# RF08old.net
KiCad netlist of a schematic drawn in EAGLE
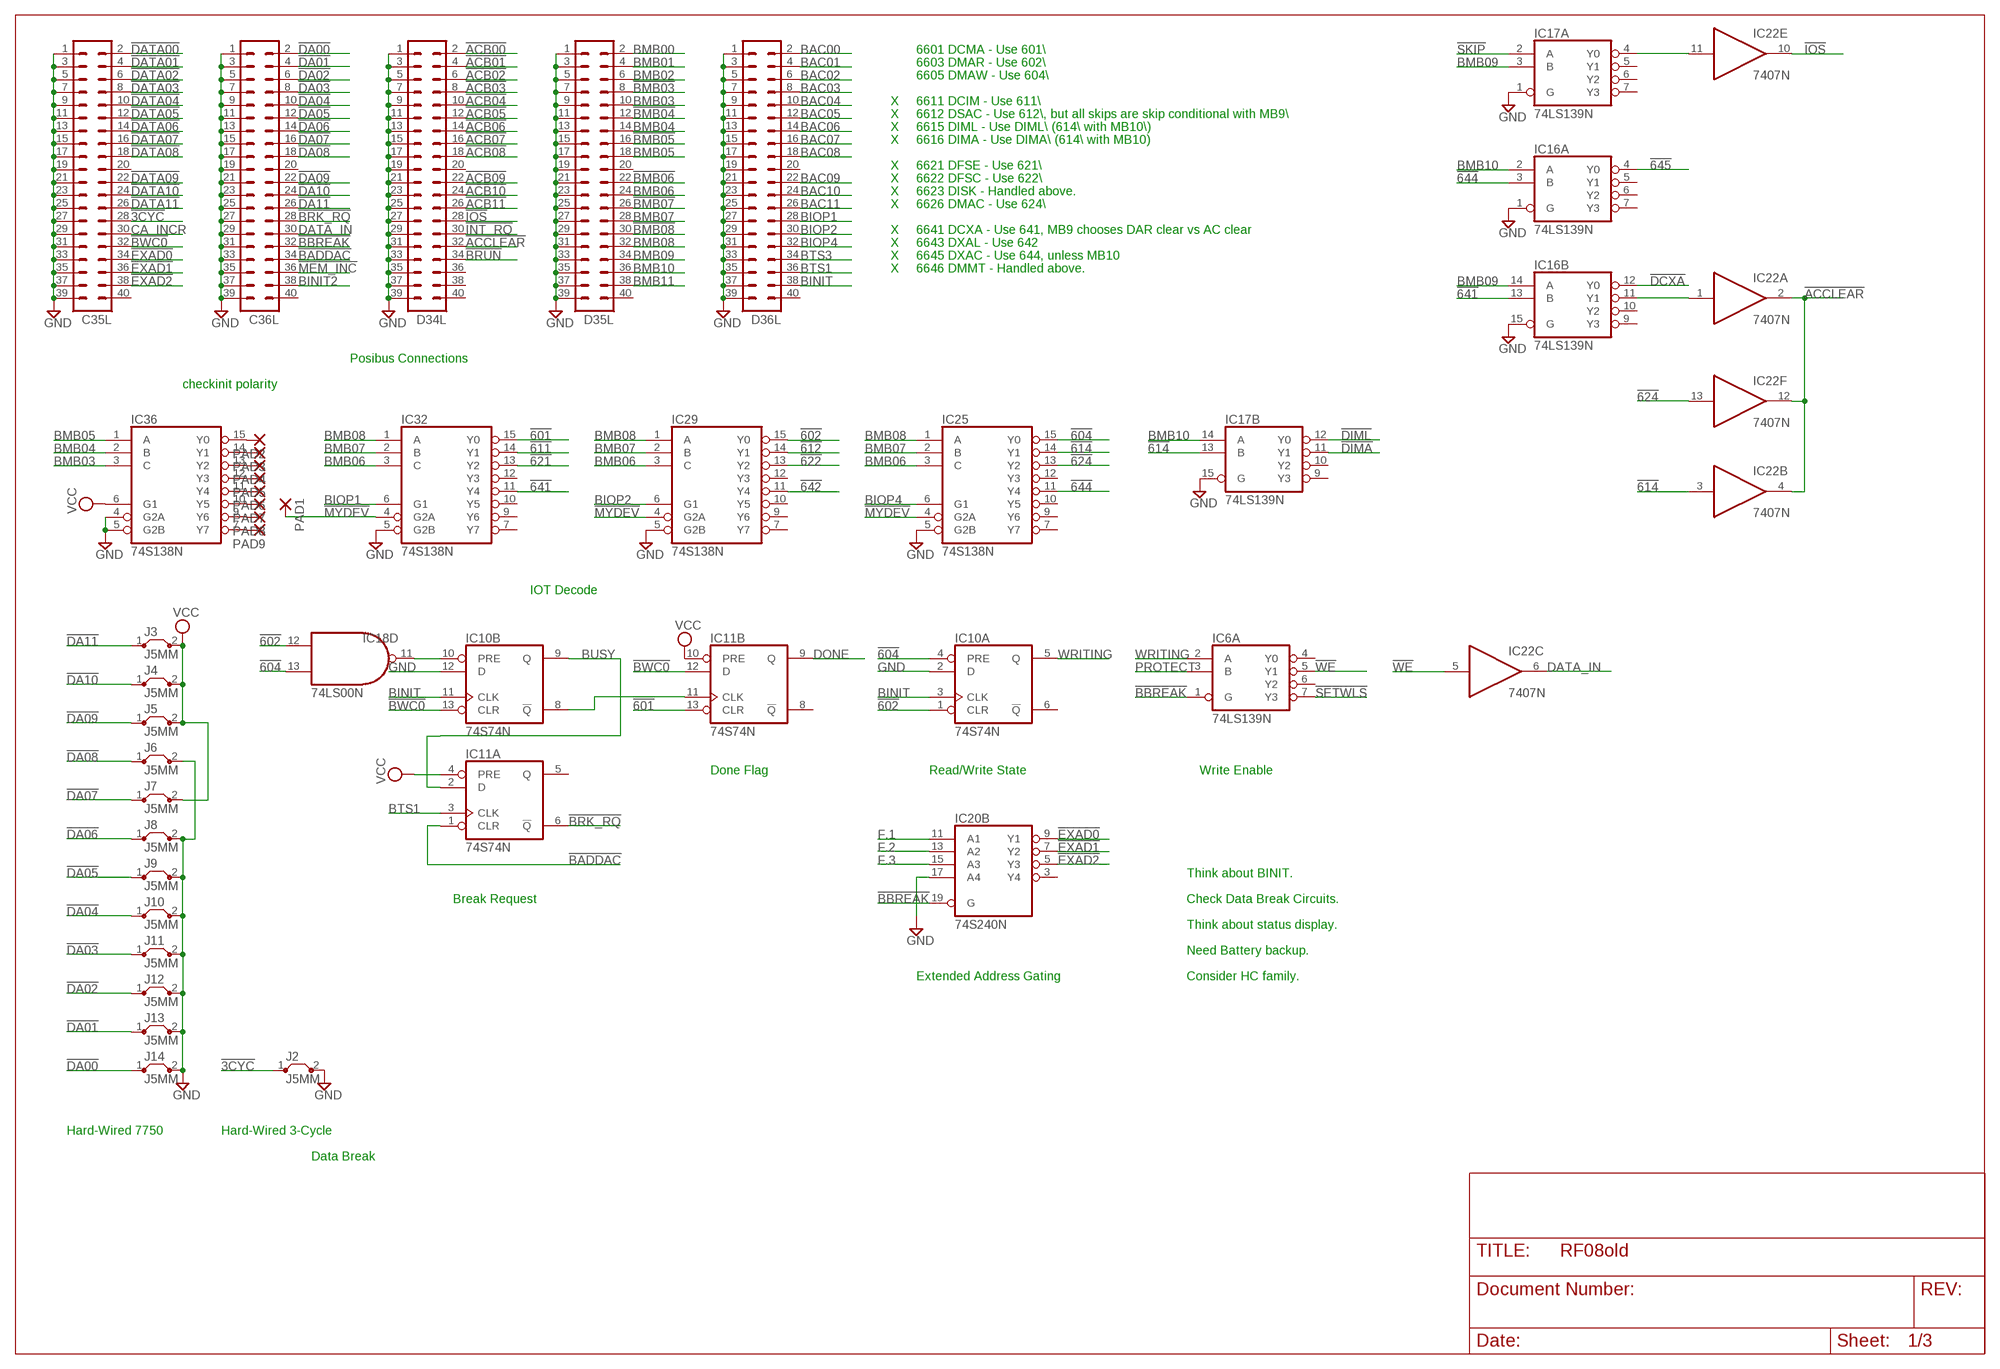
[diagram p0: schematic, sheet 1]
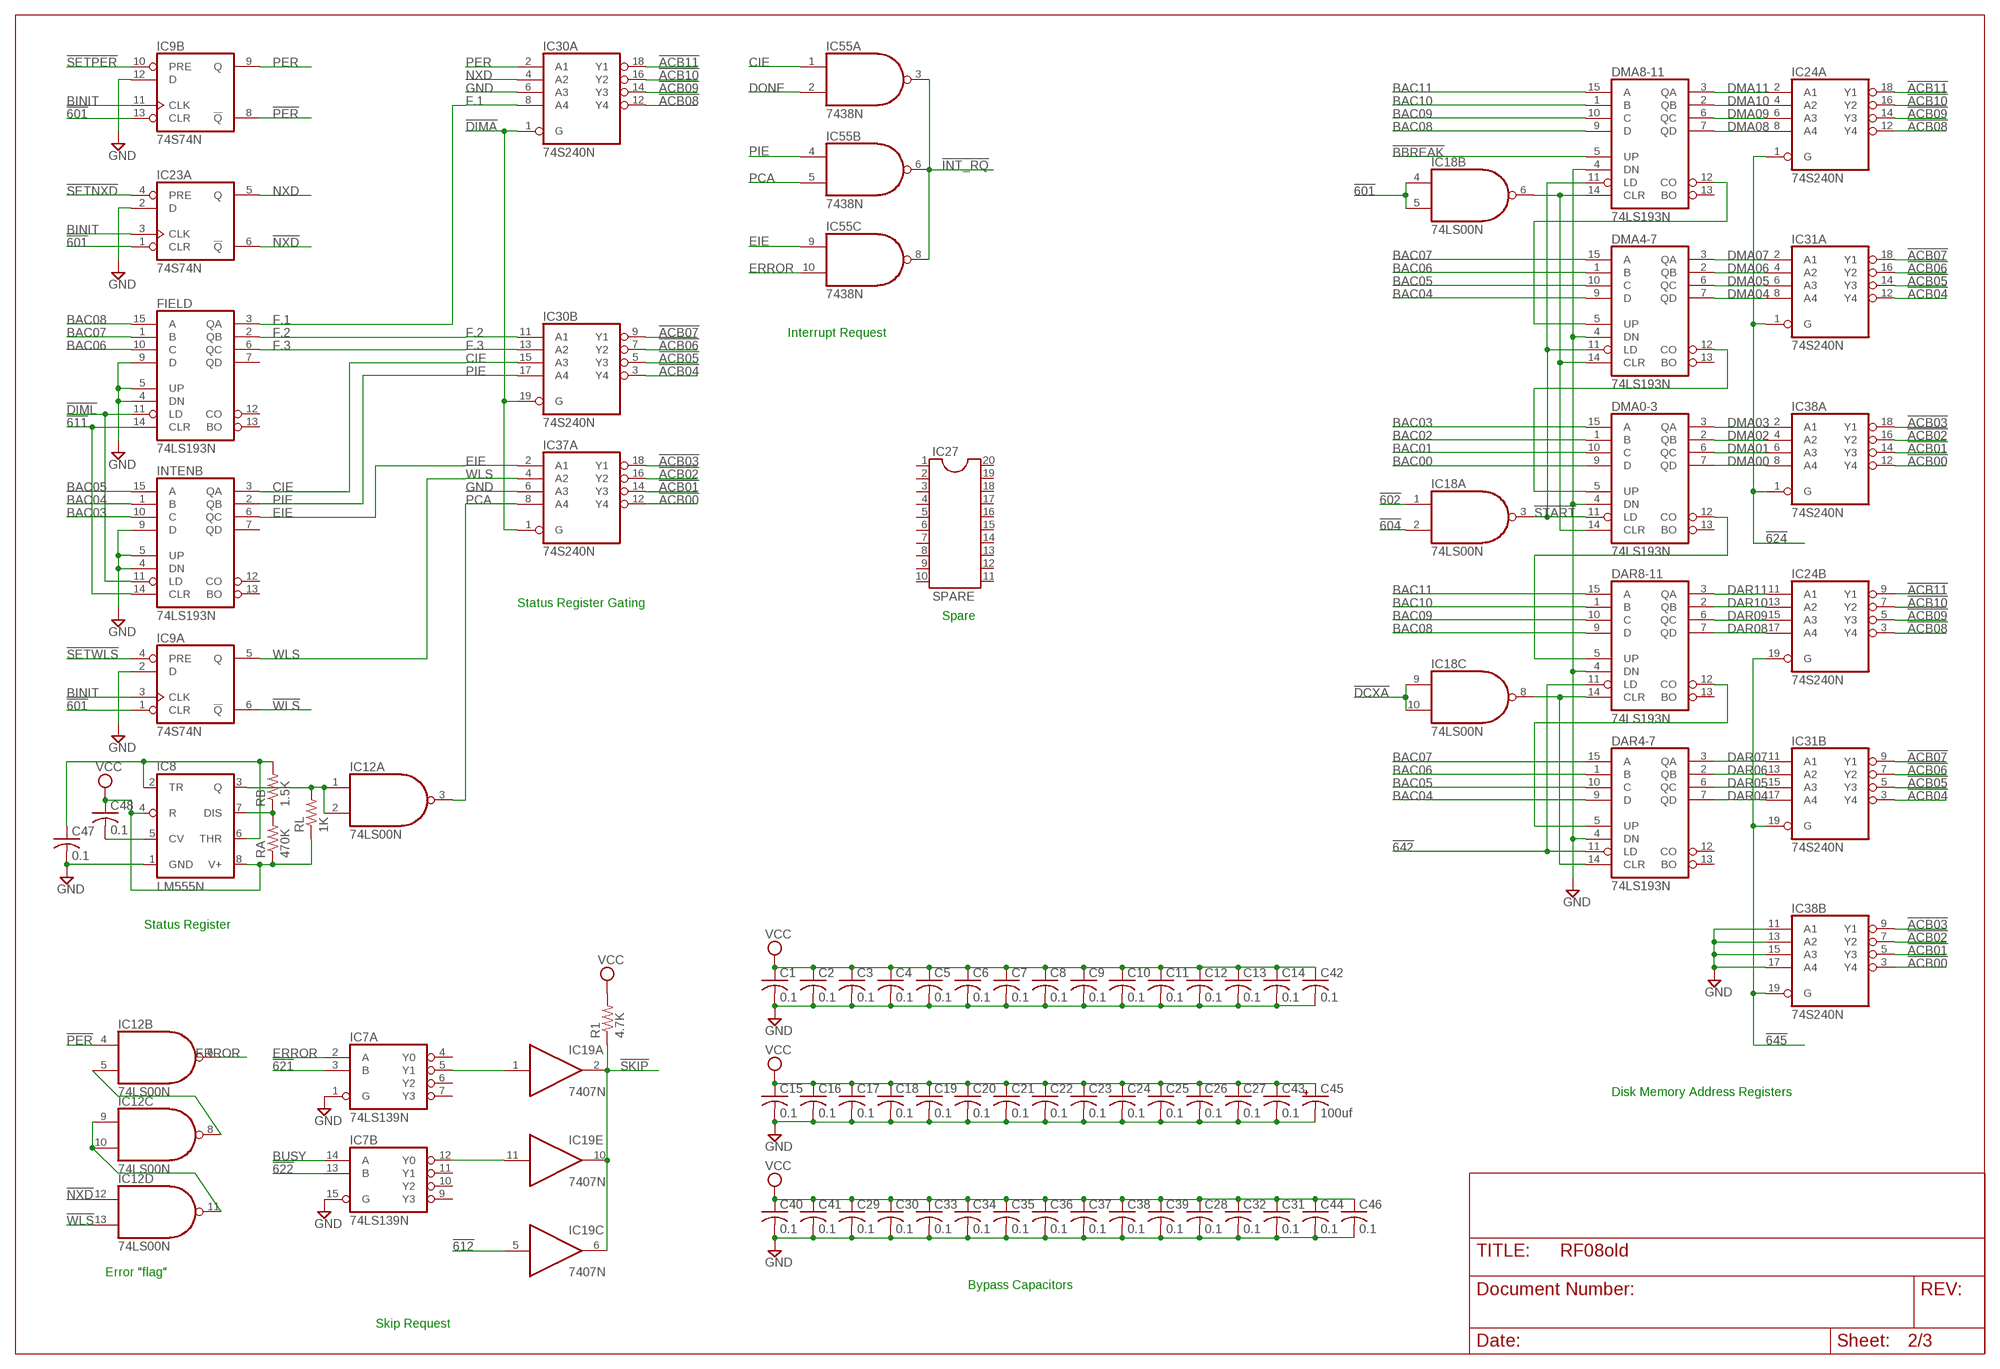
[diagram p1: schematic, sheet 2]
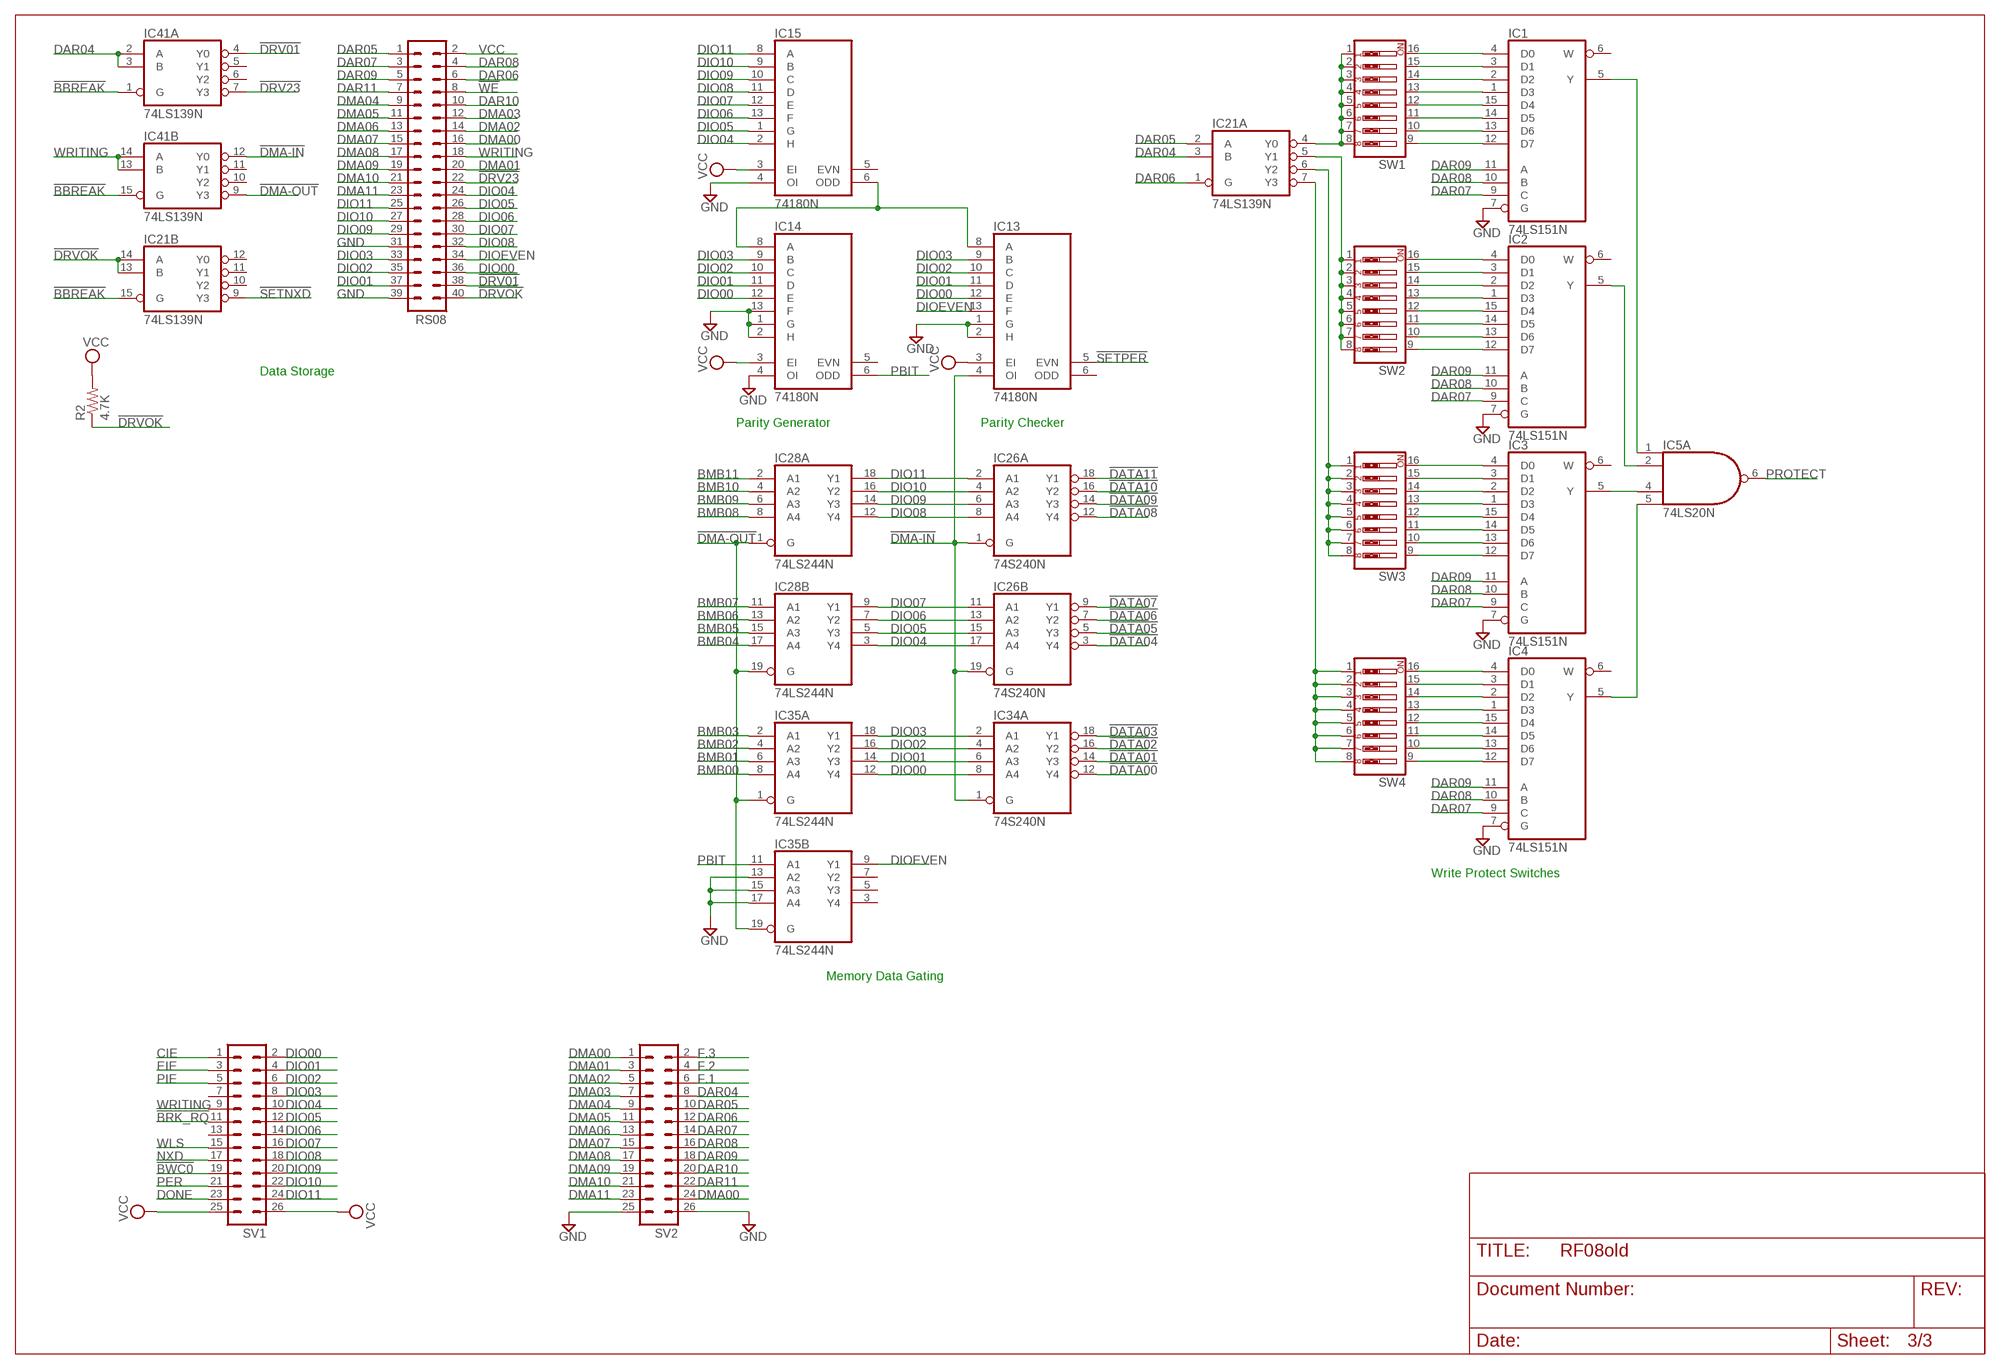
[diagram p2: schematic, sheet 3]

(export (version "E")
  (design (tool "Eeschema 10.0.6"))
  (components
    (comp (ref "C35L")
      (value "MA20-2")
      (footprint "eagle-import:MA20-2")
      (libsource (lib "eagle-import") (part "MA20-2"))
    )
    (comp (ref "C36L")
      (value "MA20-2")
      (footprint "eagle-import:MA20-2")
      (libsource (lib "eagle-import") (part "MA20-2"))
    )
    (comp (ref "D34L")
      (value "MA20-2")
      (footprint "eagle-import:MA20-2")
      (libsource (lib "eagle-import") (part "MA20-2"))
    )
    (comp (ref "D35L")
      (value "MA20-2")
      (footprint "eagle-import:MA20-2")
      (libsource (lib "eagle-import") (part "MA20-2"))
    )
    (comp (ref "D36L")
      (value "MA20-2")
      (footprint "eagle-import:MA20-2")
      (libsource (lib "eagle-import") (part "MA20-2"))
    )
    (comp (ref "IC6")
      (value "74LS139N")
      (footprint "eagle-import:DIL16")
      (libsource (lib "eagle-import") (part "74139NS"))
    )
    (comp (ref "IC10")
      (value "74S74N")
      (footprint "eagle-import:DIL14")
      (libsource (lib "eagle-import") (part "7474NS"))
    )
    (comp (ref "IC11")
      (value "74S74N")
      (footprint "eagle-import:DIL14")
      (libsource (lib "eagle-import") (part "7474NS"))
    )
    (comp (ref "IC16")
      (value "74LS139N")
      (footprint "eagle-import:DIL16")
      (libsource (lib "eagle-import") (part "74139NS"))
    )
    (comp (ref "IC17")
      (value "74LS139N")
      (footprint "eagle-import:DIL16")
      (libsource (lib "eagle-import") (part "74139NS"))
    )
    (comp (ref "IC18")
      (value "74LS00N")
      (footprint "eagle-import:DIL14")
      (libsource (lib "eagle-import") (part "7400NLS"))
    )
    (comp (ref "IC20")
      (value "74S240N")
      (footprint "eagle-import:DIL20")
      (libsource (lib "eagle-import") (part "74240NS"))
    )
    (comp (ref "IC22")
      (value "7407N")
      (footprint "eagle-import:DIL14")
      (libsource (lib "eagle-import") (part "7407N"))
    )
    (comp (ref "IC25")
      (value "74S138N")
      (footprint "eagle-import:DIL16")
      (libsource (lib "eagle-import") (part "74138NS"))
    )
    (comp (ref "IC29")
      (value "74S138N")
      (footprint "eagle-import:DIL16")
      (libsource (lib "eagle-import") (part "74138NS"))
    )
    (comp (ref "IC32")
      (value "74S138N")
      (footprint "eagle-import:DIL16")
      (libsource (lib "eagle-import") (part "74138NS"))
    )
    (comp (ref "IC36")
      (value "74S138N")
      (footprint "eagle-import:DIL16")
      (libsource (lib "eagle-import") (part "74138NS"))
    )
    (comp (ref "J2")
      (value "J5MM")
      (footprint "eagle-import:05")
      (libsource (lib "eagle-import") (part "J5MM"))
    )
    (comp (ref "J3")
      (value "J5MM")
      (footprint "eagle-import:05")
      (libsource (lib "eagle-import") (part "J5MM"))
    )
    (comp (ref "J4")
      (value "J5MM")
      (footprint "eagle-import:05")
      (libsource (lib "eagle-import") (part "J5MM"))
    )
    (comp (ref "J5")
      (value "J5MM")
      (footprint "eagle-import:05")
      (libsource (lib "eagle-import") (part "J5MM"))
    )
    (comp (ref "J6")
      (value "J5MM")
      (footprint "eagle-import:05")
      (libsource (lib "eagle-import") (part "J5MM"))
    )
    (comp (ref "J7")
      (value "J5MM")
      (footprint "eagle-import:05")
      (libsource (lib "eagle-import") (part "J5MM"))
    )
    (comp (ref "J8")
      (value "J5MM")
      (footprint "eagle-import:05")
      (libsource (lib "eagle-import") (part "J5MM"))
    )
    (comp (ref "J9")
      (value "J5MM")
      (footprint "eagle-import:05")
      (libsource (lib "eagle-import") (part "J5MM"))
    )
    (comp (ref "J10")
      (value "J5MM")
      (footprint "eagle-import:05")
      (libsource (lib "eagle-import") (part "J5MM"))
    )
    (comp (ref "J11")
      (value "J5MM")
      (footprint "eagle-import:05")
      (libsource (lib "eagle-import") (part "J5MM"))
    )
    (comp (ref "J12")
      (value "J5MM")
      (footprint "eagle-import:05")
      (libsource (lib "eagle-import") (part "J5MM"))
    )
    (comp (ref "J13")
      (value "J5MM")
      (footprint "eagle-import:05")
      (libsource (lib "eagle-import") (part "J5MM"))
    )
    (comp (ref "J14")
      (value "J5MM")
      (footprint "eagle-import:05")
      (libsource (lib "eagle-import") (part "J5MM"))
    )
    (comp (ref "PAD1")
      (value "1,6/0,8")
      (footprint "eagle-import:1,6_0,8")
      (libsource (lib "eagle-import") (part "1,6/0,8"))
    )
    (comp (ref "PAD2")
      (value "1,6/0,8")
      (footprint "eagle-import:1,6_0,8")
      (libsource (lib "eagle-import") (part "1,6/0,8"))
    )
    (comp (ref "PAD3")
      (value "1,6/0,8")
      (footprint "eagle-import:1,6_0,8")
      (libsource (lib "eagle-import") (part "1,6/0,8"))
    )
    (comp (ref "PAD4")
      (value "1,6/0,8")
      (footprint "eagle-import:1,6_0,8")
      (libsource (lib "eagle-import") (part "1,6/0,8"))
    )
    (comp (ref "PAD5")
      (value "1,6/0,8")
      (footprint "eagle-import:1,6_0,8")
      (libsource (lib "eagle-import") (part "1,6/0,8"))
    )
    (comp (ref "PAD6")
      (value "1,6/0,8")
      (footprint "eagle-import:1,6_0,8")
      (libsource (lib "eagle-import") (part "1,6/0,8"))
    )
    (comp (ref "PAD7")
      (value "1,6/0,8")
      (footprint "eagle-import:1,6_0,8")
      (libsource (lib "eagle-import") (part "1,6/0,8"))
    )
    (comp (ref "PAD8")
      (value "1,6/0,8")
      (footprint "eagle-import:1,6_0,8")
      (libsource (lib "eagle-import") (part "1,6/0,8"))
    )
    (comp (ref "PAD9")
      (value "1,6/0,8")
      (footprint "eagle-import:1,6_0,8")
      (libsource (lib "eagle-import") (part "1,6/0,8"))
    )
    (comp (ref "IC1")
      (value "74LS151N")
      (footprint "eagle-import:DIL16")
      (libsource (lib "eagle-import") (part "74151NLS"))
    )
    (comp (ref "IC2")
      (value "74LS151N")
      (footprint "eagle-import:DIL16")
      (libsource (lib "eagle-import") (part "74151NLS"))
    )
    (comp (ref "IC3")
      (value "74LS151N")
      (footprint "eagle-import:DIL16")
      (libsource (lib "eagle-import") (part "74151NLS"))
    )
    (comp (ref "IC4")
      (value "74LS151N")
      (footprint "eagle-import:DIL16")
      (libsource (lib "eagle-import") (part "74151NLS"))
    )
    (comp (ref "IC5")
      (value "74LS20N")
      (footprint "eagle-import:DIL14")
      (libsource (lib "eagle-import") (part "7420NLS"))
    )
    (comp (ref "IC13")
      (value "74180N")
      (footprint "eagle-import:DIL14")
      (libsource (lib "eagle-import") (part "74180N"))
    )
    (comp (ref "IC14")
      (value "74180N")
      (footprint "eagle-import:DIL14")
      (libsource (lib "eagle-import") (part "74180N"))
    )
    (comp (ref "IC15")
      (value "74180N")
      (footprint "eagle-import:DIL14")
      (libsource (lib "eagle-import") (part "74180N"))
    )
    (comp (ref "IC21")
      (value "74LS139N")
      (footprint "eagle-import:DIL16")
      (libsource (lib "eagle-import") (part "74139NLS"))
    )
    (comp (ref "IC26")
      (value "74S240N")
      (footprint "eagle-import:DIL20")
      (libsource (lib "eagle-import") (part "74240NS"))
    )
    (comp (ref "IC28")
      (value "74LS244N")
      (footprint "eagle-import:DIL20")
      (libsource (lib "eagle-import") (part "74244NLS"))
    )
    (comp (ref "IC34")
      (value "74S240N")
      (footprint "eagle-import:DIL20")
      (libsource (lib "eagle-import") (part "74240NS"))
    )
    (comp (ref "IC35")
      (value "74LS244N")
      (footprint "eagle-import:DIL20")
      (libsource (lib "eagle-import") (part "74244NLS"))
    )
    (comp (ref "IC41")
      (value "74LS139N")
      (footprint "eagle-import:DIL16")
      (libsource (lib "eagle-import") (part "74139NLS"))
    )
    (comp (ref "R2")
      (value "4.7K")
      (footprint "eagle-import:0207_10")
      (libsource (lib "eagle-import") (part "R-US_0207/10"))
    )
    (comp (ref "RS08")
      (value "MA20-2")
      (footprint "eagle-import:MA20-2")
      (libsource (lib "eagle-import") (part "MA20-2"))
    )
    (comp (ref "SV1")
      (value "MA13-2")
      (footprint "eagle-import:MA13-2")
      (libsource (lib "eagle-import") (part "MA13-2"))
    )
    (comp (ref "SV2")
      (value "MA13-2")
      (footprint "eagle-import:MA13-2")
      (libsource (lib "eagle-import") (part "MA13-2"))
    )
    (comp (ref "SW1")
      (value "SW_DIP-8")
      (footprint "eagle-import:EDG-08")
      (libsource (lib "eagle-import") (part "SW_DIP-8"))
    )
    (comp (ref "SW2")
      (value "SW_DIP-8")
      (footprint "eagle-import:EDG-08")
      (libsource (lib "eagle-import") (part "SW_DIP-8"))
    )
    (comp (ref "SW3")
      (value "SW_DIP-8")
      (footprint "eagle-import:EDG-08")
      (libsource (lib "eagle-import") (part "SW_DIP-8"))
    )
    (comp (ref "SW4")
      (value "SW_DIP-8")
      (footprint "eagle-import:EDG-08")
      (libsource (lib "eagle-import") (part "SW_DIP-8"))
    )
    (comp (ref "C1")
      (value "0.1")
      (footprint "eagle-import:C050-025X075")
      (libsource (lib "eagle-import") (part "C-US050-025X075"))
    )
    (comp (ref "C2")
      (value "0.1")
      (footprint "eagle-import:C050-025X075")
      (libsource (lib "eagle-import") (part "C-US050-025X075"))
    )
    (comp (ref "C3")
      (value "0.1")
      (footprint "eagle-import:C050-025X075")
      (libsource (lib "eagle-import") (part "C-US050-025X075"))
    )
    (comp (ref "C4")
      (value "0.1")
      (footprint "eagle-import:C050-025X075")
      (libsource (lib "eagle-import") (part "C-US050-025X075"))
    )
    (comp (ref "C5")
      (value "0.1")
      (footprint "eagle-import:C050-025X075")
      (libsource (lib "eagle-import") (part "C-US050-025X075"))
    )
    (comp (ref "C6")
      (value "0.1")
      (footprint "eagle-import:C050-025X075")
      (libsource (lib "eagle-import") (part "C-US050-025X075"))
    )
    (comp (ref "C7")
      (value "0.1")
      (footprint "eagle-import:C050-025X075")
      (libsource (lib "eagle-import") (part "C-US050-025X075"))
    )
    (comp (ref "C8")
      (value "0.1")
      (footprint "eagle-import:C050-025X075")
      (libsource (lib "eagle-import") (part "C-US050-025X075"))
    )
    (comp (ref "C9")
      (value "0.1")
      (footprint "eagle-import:C050-025X075")
      (libsource (lib "eagle-import") (part "C-US050-025X075"))
    )
    (comp (ref "C10")
      (value "0.1")
      (footprint "eagle-import:C050-025X075")
      (libsource (lib "eagle-import") (part "C-US050-025X075"))
    )
    (comp (ref "C11")
      (value "0.1")
      (footprint "eagle-import:C050-025X075")
      (libsource (lib "eagle-import") (part "C-US050-025X075"))
    )
    (comp (ref "C12")
      (value "0.1")
      (footprint "eagle-import:C050-025X075")
      (libsource (lib "eagle-import") (part "C-US050-025X075"))
    )
    (comp (ref "C13")
      (value "0.1")
      (footprint "eagle-import:C050-025X075")
      (libsource (lib "eagle-import") (part "C-US050-025X075"))
    )
    (comp (ref "C14")
      (value "0.1")
      (footprint "eagle-import:C050-025X075")
      (libsource (lib "eagle-import") (part "C-US050-025X075"))
    )
    (comp (ref "C15")
      (value "0.1")
      (footprint "eagle-import:C050-025X075")
      (libsource (lib "eagle-import") (part "C-US050-025X075"))
    )
    (comp (ref "C16")
      (value "0.1")
      (footprint "eagle-import:C050-025X075")
      (libsource (lib "eagle-import") (part "C-US050-025X075"))
    )
    (comp (ref "C17")
      (value "0.1")
      (footprint "eagle-import:C050-025X075")
      (libsource (lib "eagle-import") (part "C-US050-025X075"))
    )
    (comp (ref "C18")
      (value "0.1")
      (footprint "eagle-import:C050-025X075")
      (libsource (lib "eagle-import") (part "C-US050-025X075"))
    )
    (comp (ref "C19")
      (value "0.1")
      (footprint "eagle-import:C050-025X075")
      (libsource (lib "eagle-import") (part "C-US050-025X075"))
    )
    (comp (ref "C20")
      (value "0.1")
      (footprint "eagle-import:C050-025X075")
      (libsource (lib "eagle-import") (part "C-US050-025X075"))
    )
    (comp (ref "C21")
      (value "0.1")
      (footprint "eagle-import:C050-025X075")
      (libsource (lib "eagle-import") (part "C-US050-025X075"))
    )
    (comp (ref "C22")
      (value "0.1")
      (footprint "eagle-import:C050-025X075")
      (libsource (lib "eagle-import") (part "C-US050-025X075"))
    )
    (comp (ref "C23")
      (value "0.1")
      (footprint "eagle-import:C050-025X075")
      (libsource (lib "eagle-import") (part "C-US050-025X075"))
    )
    (comp (ref "C24")
      (value "0.1")
      (footprint "eagle-import:C050-025X075")
      (libsource (lib "eagle-import") (part "C-US050-025X075"))
    )
    (comp (ref "C25")
      (value "0.1")
      (footprint "eagle-import:C050-025X075")
      (libsource (lib "eagle-import") (part "C-US050-025X075"))
    )
    (comp (ref "C26")
      (value "0.1")
      (footprint "eagle-import:C050-025X075")
      (libsource (lib "eagle-import") (part "C-US050-025X075"))
    )
    (comp (ref "C27")
      (value "0.1")
      (footprint "eagle-import:C050-025X075")
      (libsource (lib "eagle-import") (part "C-US050-025X075"))
    )
    (comp (ref "C28")
      (value "0.1")
      (footprint "eagle-import:C050-025X075")
      (libsource (lib "eagle-import") (part "C-US050-025X075"))
    )
    (comp (ref "C29")
      (value "0.1")
      (footprint "eagle-import:C050-025X075")
      (libsource (lib "eagle-import") (part "C-US050-025X075"))
    )
    (comp (ref "C30")
      (value "0.1")
      (footprint "eagle-import:C050-025X075")
      (libsource (lib "eagle-import") (part "C-US050-025X075"))
    )
    (comp (ref "C31")
      (value "0.1")
      (footprint "eagle-import:C050-025X075")
      (libsource (lib "eagle-import") (part "C-US050-025X075"))
    )
    (comp (ref "C32")
      (value "0.1")
      (footprint "eagle-import:C050-025X075")
      (libsource (lib "eagle-import") (part "C-US050-025X075"))
    )
    (comp (ref "C33")
      (value "0.1")
      (footprint "eagle-import:C050-025X075")
      (libsource (lib "eagle-import") (part "C-US050-025X075"))
    )
    (comp (ref "C34")
      (value "0.1")
      (footprint "eagle-import:C050-025X075")
      (libsource (lib "eagle-import") (part "C-US050-025X075"))
    )
    (comp (ref "C35")
      (value "0.1")
      (footprint "eagle-import:C050-025X075")
      (libsource (lib "eagle-import") (part "C-US050-025X075"))
    )
    (comp (ref "C36")
      (value "0.1")
      (footprint "eagle-import:C050-025X075")
      (libsource (lib "eagle-import") (part "C-US050-025X075"))
    )
    (comp (ref "C37")
      (value "0.1")
      (footprint "eagle-import:C050-025X075")
      (libsource (lib "eagle-import") (part "C-US050-025X075"))
    )
    (comp (ref "C38")
      (value "0.1")
      (footprint "eagle-import:C050-025X075")
      (libsource (lib "eagle-import") (part "C-US050-025X075"))
    )
    (comp (ref "C39")
      (value "0.1")
      (footprint "eagle-import:C050-025X075")
      (libsource (lib "eagle-import") (part "C-US050-025X075"))
    )
    (comp (ref "C40")
      (value "0.1")
      (footprint "eagle-import:C050-025X075")
      (libsource (lib "eagle-import") (part "C-US050-025X075"))
    )
    (comp (ref "C41")
      (value "0.1")
      (footprint "eagle-import:C050-025X075")
      (libsource (lib "eagle-import") (part "C-US050-025X075"))
    )
    (comp (ref "C42")
      (value "0.1")
      (footprint "eagle-import:C050-025X075")
      (libsource (lib "eagle-import") (part "C-US050-025X075"))
    )
    (comp (ref "C43")
      (value "0.1")
      (footprint "eagle-import:C050-025X075")
      (libsource (lib "eagle-import") (part "C-US050-025X075"))
    )
    (comp (ref "C44")
      (value "0.1")
      (footprint "eagle-import:C050-025X075")
      (libsource (lib "eagle-import") (part "C-US050-025X075"))
    )
    (comp (ref "C45")
      (value "100uf")
      (footprint "eagle-import:E22-6")
      (libsource (lib "eagle-import") (part "CPOL-USE22-6AXIAL"))
    )
    (comp (ref "C46")
      (value "0.1")
      (footprint "eagle-import:C050-025X075")
      (libsource (lib "eagle-import") (part "C-US050-025X075"))
    )
    (comp (ref "C47")
      (value "0.1")
      (footprint "eagle-import:C050-025X075")
      (libsource (lib "eagle-import") (part "C-US050-025X075"))
    )
    (comp (ref "C48")
      (value "0.1")
      (footprint "eagle-import:C050-025X075")
      (libsource (lib "eagle-import") (part "C-US050-025X075"))
    )
    (comp (ref "DAR4-7")
      (value "74LS193N")
      (footprint "eagle-import:DIL16")
      (libsource (lib "eagle-import") (part "74192NLS"))
    )
    (comp (ref "DAR8-11")
      (value "74LS193N")
      (footprint "eagle-import:DIL16")
      (libsource (lib "eagle-import") (part "74192NLS"))
    )
    (comp (ref "DMA0-3")
      (value "74LS193N")
      (footprint "eagle-import:DIL16")
      (libsource (lib "eagle-import") (part "74192NLS"))
    )
    (comp (ref "DMA4-7")
      (value "74LS193N")
      (footprint "eagle-import:DIL16")
      (libsource (lib "eagle-import") (part "74192NLS"))
    )
    (comp (ref "DMA8-11")
      (value "74LS193N")
      (footprint "eagle-import:DIL16")
      (libsource (lib "eagle-import") (part "74192NLS"))
    )
    (comp (ref "FIELD")
      (value "74LS193N")
      (footprint "eagle-import:DIL16")
      (libsource (lib "eagle-import") (part "74192NLS"))
    )
    (comp (ref "IC7")
      (value "74LS139N")
      (footprint "eagle-import:DIL16")
      (libsource (lib "eagle-import") (part "74139NLS"))
    )
    (comp (ref "IC8")
      (value "LM555N")
      (footprint "eagle-import:DIL08")
      (libsource (lib "eagle-import") (part "555NLM"))
    )
    (comp (ref "IC9")
      (value "74S74N")
      (footprint "eagle-import:DIL14")
      (libsource (lib "eagle-import") (part "7474NS"))
    )
    (comp (ref "IC12")
      (value "74LS00N")
      (footprint "eagle-import:DIL14")
      (libsource (lib "eagle-import") (part "7400NLS"))
    )
    (comp (ref "IC19")
      (value "7407N")
      (footprint "eagle-import:DIL14")
      (libsource (lib "eagle-import") (part "7407N"))
    )
    (comp (ref "IC23")
      (value "74S74N")
      (footprint "eagle-import:DIL14")
      (libsource (lib "eagle-import") (part "7474NS"))
    )
    (comp (ref "IC24")
      (value "74S240N")
      (footprint "eagle-import:DIL20")
      (libsource (lib "eagle-import") (part "74240NS"))
    )
    (comp (ref "IC27")
      (value "SPARE")
      (footprint "eagle-import:DIL20")
      (libsource (lib "eagle-import") (part "DIL20"))
    )
    (comp (ref "IC30")
      (value "74S240N")
      (footprint "eagle-import:DIL20")
      (libsource (lib "eagle-import") (part "74240NS"))
    )
    (comp (ref "IC31")
      (value "74S240N")
      (footprint "eagle-import:DIL20")
      (libsource (lib "eagle-import") (part "74240NS"))
    )
    (comp (ref "IC37")
      (value "74S240N")
      (footprint "eagle-import:DIL20")
      (libsource (lib "eagle-import") (part "74240NS"))
    )
    (comp (ref "IC38")
      (value "74S240N")
      (footprint "eagle-import:DIL20")
      (libsource (lib "eagle-import") (part "74240NS"))
    )
    (comp (ref "IC55")
      (value "7438N")
      (footprint "eagle-import:DIL14")
      (libsource (lib "eagle-import") (part "7438N"))
    )
    (comp (ref "INTENB")
      (value "74LS193N")
      (footprint "eagle-import:DIL16")
      (libsource (lib "eagle-import") (part "74192NLS"))
    )
    (comp (ref "R1")
      (value "4.7K")
      (footprint "eagle-import:0207_10")
      (libsource (lib "eagle-import") (part "R-US_0207/10"))
    )
    (comp (ref "RA")
      (value "470K")
      (footprint "eagle-import:0207_10")
      (libsource (lib "eagle-import") (part "R-US_0207/10"))
    )
    (comp (ref "RB")
      (value "1.5K")
      (footprint "eagle-import:0207_10")
      (libsource (lib "eagle-import") (part "R-US_0207/10"))
    )
    (comp (ref "RL")
      (value "1K")
      (footprint "eagle-import:0207_10")
      (libsource (lib "eagle-import") (part "R-US_0207/10"))
    )
  )
  (nets
    (net (code "1") (name "BAC00") (class "Default")
      (node (ref "D36L") (pin "2") (pinfunction "2_2") (pintype "passive"))
      (node (ref "DMA0-3") (pin "9") (pinfunction "D_9") (pintype "input"))
    )
    (net (code "2") (name "BAC01") (class "Default")
      (node (ref "D36L") (pin "4") (pinfunction "4_4") (pintype "passive"))
      (node (ref "DMA0-3") (pin "10") (pinfunction "C_10") (pintype "input"))
    )
    (net (code "3") (name "BAC02") (class "Default")
      (node (ref "D36L") (pin "6") (pinfunction "6_6") (pintype "passive"))
      (node (ref "DMA0-3") (pin "1") (pinfunction "B_1") (pintype "input"))
    )
    (net (code "4") (name "BAC03") (class "Default")
      (node (ref "D36L") (pin "8") (pinfunction "8_8") (pintype "passive"))
      (node (ref "DMA0-3") (pin "15") (pinfunction "A_15") (pintype "input"))
      (node (ref "INTENB") (pin "10") (pinfunction "C_10") (pintype "input"))
    )
    (net (code "5") (name "BAC04") (class "Default")
      (node (ref "D36L") (pin "10") (pinfunction "10_10") (pintype "passive"))
      (node (ref "DAR4-7") (pin "9") (pinfunction "D_9") (pintype "input"))
      (node (ref "DMA4-7") (pin "9") (pinfunction "D_9") (pintype "input"))
      (node (ref "INTENB") (pin "1") (pinfunction "B_1") (pintype "input"))
    )
    (net (code "6") (name "BAC05") (class "Default")
      (node (ref "D36L") (pin "12") (pinfunction "12_12") (pintype "passive"))
      (node (ref "DAR4-7") (pin "10") (pinfunction "C_10") (pintype "input"))
      (node (ref "DMA4-7") (pin "10") (pinfunction "C_10") (pintype "input"))
      (node (ref "INTENB") (pin "15") (pinfunction "A_15") (pintype "input"))
    )
    (net (code "7") (name "BAC06") (class "Default")
      (node (ref "D36L") (pin "14") (pinfunction "14_14") (pintype "passive"))
      (node (ref "DAR4-7") (pin "1") (pinfunction "B_1") (pintype "input"))
      (node (ref "DMA4-7") (pin "1") (pinfunction "B_1") (pintype "input"))
      (node (ref "FIELD") (pin "10") (pinfunction "C_10") (pintype "input"))
    )
    (net (code "8") (name "BAC07") (class "Default")
      (node (ref "D36L") (pin "16") (pinfunction "16_16") (pintype "passive"))
      (node (ref "DAR4-7") (pin "15") (pinfunction "A_15") (pintype "input"))
      (node (ref "DMA4-7") (pin "15") (pinfunction "A_15") (pintype "input"))
      (node (ref "FIELD") (pin "1") (pinfunction "B_1") (pintype "input"))
    )
    (net (code "9") (name "BAC08") (class "Default")
      (node (ref "D36L") (pin "18") (pinfunction "18_18") (pintype "passive"))
      (node (ref "DAR8-11") (pin "9") (pinfunction "D_9") (pintype "input"))
      (node (ref "DMA8-11") (pin "9") (pinfunction "D_9") (pintype "input"))
      (node (ref "FIELD") (pin "15") (pinfunction "A_15") (pintype "input"))
    )
    (net (code "10") (name "BAC09") (class "Default")
      (node (ref "D36L") (pin "22") (pinfunction "22_22") (pintype "passive"))
      (node (ref "DAR8-11") (pin "10") (pinfunction "C_10") (pintype "input"))
      (node (ref "DMA8-11") (pin "10") (pinfunction "C_10") (pintype "input"))
    )
    (net (code "11") (name "BAC10") (class "Default")
      (node (ref "D36L") (pin "24") (pinfunction "24_24") (pintype "passive"))
      (node (ref "DAR8-11") (pin "1") (pinfunction "B_1") (pintype "input"))
      (node (ref "DMA8-11") (pin "1") (pinfunction "B_1") (pintype "input"))
    )
    (net (code "12") (name "BAC11") (class "Default")
      (node (ref "D36L") (pin "26") (pinfunction "26_26") (pintype "passive"))
      (node (ref "DAR8-11") (pin "15") (pinfunction "A_15") (pintype "input"))
      (node (ref "DMA8-11") (pin "15") (pinfunction "A_15") (pintype "input"))
    )
    (net (code "13") (name "BINIT") (class "Default")
      (node (ref "D36L") (pin "38") (pinfunction "38_38") (pintype "passive"))
      (node (ref "IC10") (pin "11") (pinfunction "CLK_11") (pintype "input"))
      (node (ref "IC10") (pin "3") (pinfunction "CLK_3") (pintype "input"))
      (node (ref "IC23") (pin "3") (pinfunction "CLK_3") (pintype "input"))
      (node (ref "IC9") (pin "11") (pinfunction "CLK_11") (pintype "input"))
      (node (ref "IC9") (pin "3") (pinfunction "CLK_3") (pintype "input"))
    )
    (net (code "14") (name "BINIT2") (class "Default")
      (node (ref "C36L") (pin "38") (pinfunction "38_38") (pintype "passive"))
    )
    (net (code "15") (name "BIOP1") (class "Default")
      (node (ref "D36L") (pin "28") (pinfunction "28_28") (pintype "passive"))
      (node (ref "IC32") (pin "6") (pinfunction "G1_6") (pintype "input"))
    )
    (net (code "16") (name "BIOP2") (class "Default")
      (node (ref "D36L") (pin "30") (pinfunction "30_30") (pintype "passive"))
      (node (ref "IC29") (pin "6") (pinfunction "G1_6") (pintype "input"))
    )
    (net (code "17") (name "BIOP4") (class "Default")
      (node (ref "D36L") (pin "32") (pinfunction "32_32") (pintype "passive"))
      (node (ref "IC25") (pin "6") (pinfunction "G1_6") (pintype "input"))
    )
    (net (code "18") (name "BMB00") (class "Default")
      (node (ref "D35L") (pin "2") (pinfunction "2_2") (pintype "passive"))
      (node (ref "IC35") (pin "8") (pinfunction "A4_8") (pintype "input"))
    )
    (net (code "19") (name "BMB01") (class "Default")
      (node (ref "D35L") (pin "4") (pinfunction "4_4") (pintype "passive"))
      (node (ref "IC35") (pin "6") (pinfunction "A3_6") (pintype "input"))
    )
    (net (code "20") (name "BMB02") (class "Default")
      (node (ref "D35L") (pin "6") (pinfunction "6_6") (pintype "passive"))
      (node (ref "IC35") (pin "4") (pinfunction "A2_4") (pintype "input"))
    )
    (net (code "21") (name "BMB03") (class "Default")
      (node (ref "D35L") (pin "10") (pinfunction "10_10") (pintype "passive"))
      (node (ref "IC35") (pin "2") (pinfunction "A1_2") (pintype "input"))
      (node (ref "IC36") (pin "3") (pinfunction "C_3") (pintype "input"))
    )
    (net (code "22") (name "BMB04") (class "Default")
      (node (ref "D35L") (pin "14") (pinfunction "14_14") (pintype "passive"))
      (node (ref "IC28") (pin "17") (pinfunction "A4_17") (pintype "input"))
      (node (ref "IC36") (pin "2") (pinfunction "B_2") (pintype "input"))
    )
    (net (code "23") (name "BMB05") (class "Default")
      (node (ref "D35L") (pin "18") (pinfunction "18_18") (pintype "passive"))
      (node (ref "IC28") (pin "15") (pinfunction "A3_15") (pintype "input"))
      (node (ref "IC36") (pin "1") (pinfunction "A_1") (pintype "input"))
    )
    (net (code "24") (name "BMB06") (class "Default")
      (node (ref "D35L") (pin "24") (pinfunction "24_24") (pintype "passive"))
      (node (ref "IC25") (pin "3") (pinfunction "C_3") (pintype "input"))
      (node (ref "IC28") (pin "13") (pinfunction "A2_13") (pintype "input"))
      (node (ref "IC29") (pin "3") (pinfunction "C_3") (pintype "input"))
      (node (ref "IC32") (pin "3") (pinfunction "C_3") (pintype "input"))
    )
    (net (code "25") (name "BMB07") (class "Default")
      (node (ref "D35L") (pin "28") (pinfunction "28_28") (pintype "passive"))
      (node (ref "IC25") (pin "2") (pinfunction "B_2") (pintype "input"))
      (node (ref "IC28") (pin "11") (pinfunction "A1_11") (pintype "input"))
      (node (ref "IC29") (pin "2") (pinfunction "B_2") (pintype "input"))
      (node (ref "IC32") (pin "2") (pinfunction "B_2") (pintype "input"))
    )
    (net (code "26") (name "BMB08") (class "Default")
      (node (ref "D35L") (pin "32") (pinfunction "32_32") (pintype "passive"))
      (node (ref "IC25") (pin "1") (pinfunction "A_1") (pintype "input"))
      (node (ref "IC28") (pin "8") (pinfunction "A4_8") (pintype "input"))
      (node (ref "IC29") (pin "1") (pinfunction "A_1") (pintype "input"))
      (node (ref "IC32") (pin "1") (pinfunction "A_1") (pintype "input"))
    )
    (net (code "27") (name "BMB09") (class "Default")
      (node (ref "D35L") (pin "34") (pinfunction "34_34") (pintype "passive"))
      (node (ref "IC16") (pin "14") (pinfunction "A_14") (pintype "input"))
      (node (ref "IC17") (pin "3") (pinfunction "B_3") (pintype "input"))
      (node (ref "IC28") (pin "6") (pinfunction "A3_6") (pintype "input"))
    )
    (net (code "28") (name "BMB10") (class "Default")
      (node (ref "D35L") (pin "36") (pinfunction "36_36") (pintype "passive"))
      (node (ref "IC16") (pin "2") (pinfunction "A_2") (pintype "input"))
      (node (ref "IC17") (pin "14") (pinfunction "A_14") (pintype "input"))
      (node (ref "IC28") (pin "4") (pinfunction "A2_4") (pintype "input"))
    )
    (net (code "29") (name "BMB11") (class "Default")
      (node (ref "D35L") (pin "38") (pinfunction "38_38") (pintype "passive"))
      (node (ref "IC28") (pin "2") (pinfunction "A1_2") (pintype "input"))
    )
    (net (code "30") (name "BTS1") (class "Default")
      (node (ref "D36L") (pin "36") (pinfunction "36_36") (pintype "passive"))
      (node (ref "IC11") (pin "3") (pinfunction "CLK_3") (pintype "input"))
    )
    (net (code "31") (name "BTS3") (class "Default")
      (node (ref "D36L") (pin "34") (pinfunction "34_34") (pintype "passive"))
    )
    (net (code "32") (name "BUSY") (class "Default")
      (node (ref "IC10") (pin "9") (pinfunction "Q_9") (pintype "output"))
      (node (ref "IC11") (pin "2") (pinfunction "D_2") (pintype "input"))
      (node (ref "IC7") (pin "14") (pinfunction "A_14") (pintype "input"))
    )
    (net (code "33") (name "CA_INCR") (class "Default")
      (node (ref "C35L") (pin "30") (pinfunction "30_30") (pintype "passive"))
    )
    (net (code "34") (name "CIE") (class "Default")
      (node (ref "IC30") (pin "15") (pinfunction "A3_15") (pintype "input"))
      (node (ref "IC55") (pin "1") (pinfunction "I0_1") (pintype "input"))
      (node (ref "INTENB") (pin "3") (pinfunction "QA_3") (pintype "output"))
      (node (ref "SV1") (pin "1") (pinfunction "1_1") (pintype "passive"))
    )
    (net (code "35") (name "DAR04") (class "Default")
      (node (ref "DAR4-7") (pin "7") (pinfunction "QD_7") (pintype "output"))
      (node (ref "IC21") (pin "3") (pinfunction "B_3") (pintype "input"))
      (node (ref "IC31") (pin "17") (pinfunction "A4_17") (pintype "input"))
      (node (ref "IC41") (pin "2") (pinfunction "A_2") (pintype "input"))
      (node (ref "IC41") (pin "3") (pinfunction "B_3") (pintype "input"))
      (node (ref "SV2") (pin "8") (pinfunction "8_8") (pintype "passive"))
    )
    (net (code "36") (name "DAR05") (class "Default")
      (node (ref "DAR4-7") (pin "6") (pinfunction "QC_6") (pintype "output"))
      (node (ref "IC21") (pin "2") (pinfunction "A_2") (pintype "input"))
      (node (ref "IC31") (pin "15") (pinfunction "A3_15") (pintype "input"))
      (node (ref "RS08") (pin "1") (pinfunction "1_1") (pintype "passive"))
      (node (ref "SV2") (pin "10") (pinfunction "10_10") (pintype "passive"))
    )
    (net (code "37") (name "DAR06") (class "Default")
      (node (ref "DAR4-7") (pin "2") (pinfunction "QB_2") (pintype "output"))
      (node (ref "IC21") (pin "1") (pinfunction "G_1") (pintype "input"))
      (node (ref "IC31") (pin "13") (pinfunction "A2_13") (pintype "input"))
      (node (ref "RS08") (pin "6") (pinfunction "6_6") (pintype "passive"))
      (node (ref "SV2") (pin "12") (pinfunction "12_12") (pintype "passive"))
    )
    (net (code "38") (name "DAR07") (class "Default")
      (node (ref "DAR4-7") (pin "3") (pinfunction "QA_3") (pintype "output"))
      (node (ref "IC1") (pin "9") (pinfunction "C_9") (pintype "input"))
      (node (ref "IC2") (pin "9") (pinfunction "C_9") (pintype "input"))
      (node (ref "IC3") (pin "9") (pinfunction "C_9") (pintype "input"))
      (node (ref "IC31") (pin "11") (pinfunction "A1_11") (pintype "input"))
      (node (ref "IC4") (pin "9") (pinfunction "C_9") (pintype "input"))
      (node (ref "RS08") (pin "3") (pinfunction "3_3") (pintype "passive"))
      (node (ref "SV2") (pin "14") (pinfunction "14_14") (pintype "passive"))
    )
    (net (code "39") (name "DAR08") (class "Default")
      (node (ref "DAR8-11") (pin "7") (pinfunction "QD_7") (pintype "output"))
      (node (ref "IC1") (pin "10") (pinfunction "B_10") (pintype "input"))
      (node (ref "IC2") (pin "10") (pinfunction "B_10") (pintype "input"))
      (node (ref "IC24") (pin "17") (pinfunction "A4_17") (pintype "input"))
      (node (ref "IC3") (pin "10") (pinfunction "B_10") (pintype "input"))
      (node (ref "IC4") (pin "10") (pinfunction "B_10") (pintype "input"))
      (node (ref "RS08") (pin "4") (pinfunction "4_4") (pintype "passive"))
      (node (ref "SV2") (pin "16") (pinfunction "16_16") (pintype "passive"))
    )
    (net (code "40") (name "DAR09") (class "Default")
      (node (ref "DAR8-11") (pin "6") (pinfunction "QC_6") (pintype "output"))
      (node (ref "IC1") (pin "11") (pinfunction "A_11") (pintype "input"))
      (node (ref "IC2") (pin "11") (pinfunction "A_11") (pintype "input"))
      (node (ref "IC24") (pin "15") (pinfunction "A3_15") (pintype "input"))
      (node (ref "IC3") (pin "11") (pinfunction "A_11") (pintype "input"))
      (node (ref "IC4") (pin "11") (pinfunction "A_11") (pintype "input"))
      (node (ref "RS08") (pin "5") (pinfunction "5_5") (pintype "passive"))
      (node (ref "SV2") (pin "18") (pinfunction "18_18") (pintype "passive"))
    )
    (net (code "41") (name "DAR10") (class "Default")
      (node (ref "DAR8-11") (pin "2") (pinfunction "QB_2") (pintype "output"))
      (node (ref "IC24") (pin "13") (pinfunction "A2_13") (pintype "input"))
      (node (ref "RS08") (pin "10") (pinfunction "10_10") (pintype "passive"))
      (node (ref "SV2") (pin "20") (pinfunction "20_20") (pintype "passive"))
    )
    (net (code "42") (name "DAR11") (class "Default")
      (node (ref "DAR8-11") (pin "3") (pinfunction "QA_3") (pintype "output"))
      (node (ref "IC24") (pin "11") (pinfunction "A1_11") (pintype "input"))
      (node (ref "RS08") (pin "7") (pinfunction "7_7") (pintype "passive"))
      (node (ref "SV2") (pin "22") (pinfunction "22_22") (pintype "passive"))
    )
    (net (code "43") (name "DATA_IN") (class "Default")
      (node (ref "C36L") (pin "30") (pinfunction "30_30") (pintype "passive"))
      (node (ref "IC22") (pin "6") (pinfunction "O_6") (pintype "open_collector"))
    )
    (net (code "44") (name "DIO00") (class "Default")
      (node (ref "IC13") (pin "12") (pinfunction "E_12") (pintype "input"))
      (node (ref "IC14") (pin "12") (pinfunction "E_12") (pintype "input"))
      (node (ref "IC34") (pin "8") (pinfunction "A4_8") (pintype "input"))
      (node (ref "IC35") (pin "12") (pinfunction "Y4_12") (pintype "tri_state"))
      (node (ref "RS08") (pin "36") (pinfunction "36_36") (pintype "passive"))
      (node (ref "SV1") (pin "2") (pinfunction "2_2") (pintype "passive"))
    )
    (net (code "45") (name "DIO01") (class "Default")
      (node (ref "IC13") (pin "11") (pinfunction "D_11") (pintype "input"))
      (node (ref "IC14") (pin "11") (pinfunction "D_11") (pintype "input"))
      (node (ref "IC34") (pin "6") (pinfunction "A3_6") (pintype "input"))
      (node (ref "IC35") (pin "14") (pinfunction "Y3_14") (pintype "tri_state"))
      (node (ref "RS08") (pin "37") (pinfunction "37_37") (pintype "passive"))
      (node (ref "SV1") (pin "4") (pinfunction "4_4") (pintype "passive"))
    )
    (net (code "46") (name "DIO02") (class "Default")
      (node (ref "IC13") (pin "10") (pinfunction "C_10") (pintype "input"))
      (node (ref "IC14") (pin "10") (pinfunction "C_10") (pintype "input"))
      (node (ref "IC34") (pin "4") (pinfunction "A2_4") (pintype "input"))
      (node (ref "IC35") (pin "16") (pinfunction "Y2_16") (pintype "tri_state"))
      (node (ref "RS08") (pin "35") (pinfunction "35_35") (pintype "passive"))
      (node (ref "SV1") (pin "6") (pinfunction "6_6") (pintype "passive"))
    )
    (net (code "47") (name "DIO03") (class "Default")
      (node (ref "IC13") (pin "9") (pinfunction "B_9") (pintype "input"))
      (node (ref "IC14") (pin "9") (pinfunction "B_9") (pintype "input"))
      (node (ref "IC34") (pin "2") (pinfunction "A1_2") (pintype "input"))
      (node (ref "IC35") (pin "18") (pinfunction "Y1_18") (pintype "tri_state"))
      (node (ref "RS08") (pin "33") (pinfunction "33_33") (pintype "passive"))
      (node (ref "SV1") (pin "8") (pinfunction "8_8") (pintype "passive"))
    )
    (net (code "48") (name "DIO04") (class "Default")
      (node (ref "IC15") (pin "2") (pinfunction "H_2") (pintype "input"))
      (node (ref "IC26") (pin "17") (pinfunction "A4_17") (pintype "input"))
      (node (ref "IC28") (pin "3") (pinfunction "Y4_3") (pintype "tri_state"))
      (node (ref "RS08") (pin "24") (pinfunction "24_24") (pintype "passive"))
      (node (ref "SV1") (pin "10") (pinfunction "10_10") (pintype "passive"))
    )
    (net (code "49") (name "DIO05") (class "Default")
      (node (ref "IC15") (pin "1") (pinfunction "G_1") (pintype "input"))
      (node (ref "IC26") (pin "15") (pinfunction "A3_15") (pintype "input"))
      (node (ref "IC28") (pin "5") (pinfunction "Y3_5") (pintype "tri_state"))
      (node (ref "RS08") (pin "26") (pinfunction "26_26") (pintype "passive"))
      (node (ref "SV1") (pin "12") (pinfunction "12_12") (pintype "passive"))
    )
    (net (code "50") (name "DIO06") (class "Default")
      (node (ref "IC15") (pin "13") (pinfunction "F_13") (pintype "input"))
      (node (ref "IC26") (pin "13") (pinfunction "A2_13") (pintype "input"))
      (node (ref "IC28") (pin "7") (pinfunction "Y2_7") (pintype "tri_state"))
      (node (ref "RS08") (pin "28") (pinfunction "28_28") (pintype "passive"))
      (node (ref "SV1") (pin "14") (pinfunction "14_14") (pintype "passive"))
    )
    (net (code "51") (name "DIO07") (class "Default")
      (node (ref "IC15") (pin "12") (pinfunction "E_12") (pintype "input"))
      (node (ref "IC26") (pin "11") (pinfunction "A1_11") (pintype "input"))
      (node (ref "IC28") (pin "9") (pinfunction "Y1_9") (pintype "tri_state"))
      (node (ref "RS08") (pin "30") (pinfunction "30_30") (pintype "passive"))
      (node (ref "SV1") (pin "16") (pinfunction "16_16") (pintype "passive"))
    )
    (net (code "52") (name "DIO08") (class "Default")
      (node (ref "IC15") (pin "11") (pinfunction "D_11") (pintype "input"))
      (node (ref "IC26") (pin "8") (pinfunction "A4_8") (pintype "input"))
      (node (ref "IC28") (pin "12") (pinfunction "Y4_12") (pintype "tri_state"))
      (node (ref "RS08") (pin "32") (pinfunction "32_32") (pintype "passive"))
      (node (ref "SV1") (pin "18") (pinfunction "18_18") (pintype "passive"))
    )
    (net (code "53") (name "DIO09") (class "Default")
      (node (ref "IC15") (pin "10") (pinfunction "C_10") (pintype "input"))
      (node (ref "IC26") (pin "6") (pinfunction "A3_6") (pintype "input"))
      (node (ref "IC28") (pin "14") (pinfunction "Y3_14") (pintype "tri_state"))
      (node (ref "RS08") (pin "29") (pinfunction "29_29") (pintype "passive"))
      (node (ref "SV1") (pin "20") (pinfunction "20_20") (pintype "passive"))
    )
    (net (code "54") (name "DIO10") (class "Default")
      (node (ref "IC15") (pin "9") (pinfunction "B_9") (pintype "input"))
      (node (ref "IC26") (pin "4") (pinfunction "A2_4") (pintype "input"))
      (node (ref "IC28") (pin "16") (pinfunction "Y2_16") (pintype "tri_state"))
      (node (ref "RS08") (pin "27") (pinfunction "27_27") (pintype "passive"))
      (node (ref "SV1") (pin "22") (pinfunction "22_22") (pintype "passive"))
    )
    (net (code "55") (name "DIO11") (class "Default")
      (node (ref "IC15") (pin "8") (pinfunction "A_8") (pintype "input"))
      (node (ref "IC26") (pin "2") (pinfunction "A1_2") (pintype "input"))
      (node (ref "IC28") (pin "18") (pinfunction "Y1_18") (pintype "tri_state"))
      (node (ref "RS08") (pin "25") (pinfunction "25_25") (pintype "passive"))
      (node (ref "SV1") (pin "24") (pinfunction "24_24") (pintype "passive"))
    )
    (net (code "56") (name "DIOEVEN") (class "Default")
      (node (ref "IC13") (pin "13") (pinfunction "F_13") (pintype "input"))
      (node (ref "IC35") (pin "9") (pinfunction "Y1_9") (pintype "tri_state"))
      (node (ref "RS08") (pin "34") (pinfunction "34_34") (pintype "passive"))
    )
    (net (code "57") (name "DMA00") (class "Default")
      (node (ref "DMA0-3") (pin "7") (pinfunction "QD_7") (pintype "output"))
      (node (ref "IC38") (pin "8") (pinfunction "A4_8") (pintype "input"))
      (node (ref "RS08") (pin "16") (pinfunction "16_16") (pintype "passive"))
      (node (ref "SV2") (pin "1") (pinfunction "1_1") (pintype "passive"))
      (node (ref "SV2") (pin "24") (pinfunction "24_24") (pintype "passive"))
    )
    (net (code "58") (name "DMA01") (class "Default")
      (node (ref "DMA0-3") (pin "6") (pinfunction "QC_6") (pintype "output"))
      (node (ref "IC38") (pin "6") (pinfunction "A3_6") (pintype "input"))
      (node (ref "RS08") (pin "20") (pinfunction "20_20") (pintype "passive"))
      (node (ref "SV2") (pin "3") (pinfunction "3_3") (pintype "passive"))
    )
    (net (code "59") (name "DMA02") (class "Default")
      (node (ref "DMA0-3") (pin "2") (pinfunction "QB_2") (pintype "output"))
      (node (ref "IC38") (pin "4") (pinfunction "A2_4") (pintype "input"))
      (node (ref "RS08") (pin "14") (pinfunction "14_14") (pintype "passive"))
      (node (ref "SV2") (pin "5") (pinfunction "5_5") (pintype "passive"))
    )
    (net (code "60") (name "DMA03") (class "Default")
      (node (ref "DMA0-3") (pin "3") (pinfunction "QA_3") (pintype "output"))
      (node (ref "IC38") (pin "2") (pinfunction "A1_2") (pintype "input"))
      (node (ref "RS08") (pin "12") (pinfunction "12_12") (pintype "passive"))
      (node (ref "SV2") (pin "7") (pinfunction "7_7") (pintype "passive"))
    )
    (net (code "61") (name "DMA04") (class "Default")
      (node (ref "DMA4-7") (pin "7") (pinfunction "QD_7") (pintype "output"))
      (node (ref "IC31") (pin "8") (pinfunction "A4_8") (pintype "input"))
      (node (ref "RS08") (pin "9") (pinfunction "9_9") (pintype "passive"))
      (node (ref "SV2") (pin "9") (pinfunction "9_9") (pintype "passive"))
    )
    (net (code "62") (name "DMA05") (class "Default")
      (node (ref "DMA4-7") (pin "6") (pinfunction "QC_6") (pintype "output"))
      (node (ref "IC31") (pin "6") (pinfunction "A3_6") (pintype "input"))
      (node (ref "RS08") (pin "11") (pinfunction "11_11") (pintype "passive"))
      (node (ref "SV2") (pin "11") (pinfunction "11_11") (pintype "passive"))
    )
    (net (code "63") (name "DMA06") (class "Default")
      (node (ref "DMA4-7") (pin "2") (pinfunction "QB_2") (pintype "output"))
      (node (ref "IC31") (pin "4") (pinfunction "A2_4") (pintype "input"))
      (node (ref "RS08") (pin "13") (pinfunction "13_13") (pintype "passive"))
      (node (ref "SV2") (pin "13") (pinfunction "13_13") (pintype "passive"))
    )
    (net (code "64") (name "DMA07") (class "Default")
      (node (ref "DMA4-7") (pin "3") (pinfunction "QA_3") (pintype "output"))
      (node (ref "IC31") (pin "2") (pinfunction "A1_2") (pintype "input"))
      (node (ref "RS08") (pin "15") (pinfunction "15_15") (pintype "passive"))
      (node (ref "SV2") (pin "15") (pinfunction "15_15") (pintype "passive"))
    )
    (net (code "65") (name "DMA08") (class "Default")
      (node (ref "DMA8-11") (pin "7") (pinfunction "QD_7") (pintype "output"))
      (node (ref "IC24") (pin "8") (pinfunction "A4_8") (pintype "input"))
      (node (ref "RS08") (pin "17") (pinfunction "17_17") (pintype "passive"))
      (node (ref "SV2") (pin "17") (pinfunction "17_17") (pintype "passive"))
    )
    (net (code "66") (name "DMA09") (class "Default")
      (node (ref "DMA8-11") (pin "6") (pinfunction "QC_6") (pintype "output"))
      (node (ref "IC24") (pin "6") (pinfunction "A3_6") (pintype "input"))
      (node (ref "RS08") (pin "19") (pinfunction "19_19") (pintype "passive"))
      (node (ref "SV2") (pin "19") (pinfunction "19_19") (pintype "passive"))
    )
    (net (code "67") (name "DMA10") (class "Default")
      (node (ref "DMA8-11") (pin "2") (pinfunction "QB_2") (pintype "output"))
      (node (ref "IC24") (pin "4") (pinfunction "A2_4") (pintype "input"))
      (node (ref "RS08") (pin "21") (pinfunction "21_21") (pintype "passive"))
      (node (ref "SV2") (pin "21") (pinfunction "21_21") (pintype "passive"))
    )
    (net (code "68") (name "DMA11") (class "Default")
      (node (ref "DMA8-11") (pin "3") (pinfunction "QA_3") (pintype "output"))
      (node (ref "IC24") (pin "2") (pinfunction "A1_2") (pintype "input"))
      (node (ref "RS08") (pin "23") (pinfunction "23_23") (pintype "passive"))
      (node (ref "SV2") (pin "23") (pinfunction "23_23") (pintype "passive"))
    )
    (net (code "69") (name "DONE") (class "Default")
      (node (ref "IC11") (pin "9") (pinfunction "Q_9") (pintype "output"))
      (node (ref "IC55") (pin "2") (pinfunction "I1_2") (pintype "input"))
      (node (ref "SV1") (pin "23") (pinfunction "23_23") (pintype "passive"))
    )
    (net (code "70") (name "EIE") (class "Default")
      (node (ref "IC37") (pin "2") (pinfunction "A1_2") (pintype "input"))
      (node (ref "IC55") (pin "9") (pinfunction "I0_9") (pintype "input"))
      (node (ref "INTENB") (pin "6") (pinfunction "QC_6") (pintype "output"))
      (node (ref "SV1") (pin "3") (pinfunction "3_3") (pintype "passive"))
    )
    (net (code "71") (name "ERROR") (class "Default")
      (node (ref "IC12") (pin "6") (pinfunction "O_6") (pintype "output"))
      (node (ref "IC55") (pin "10") (pinfunction "I1_10") (pintype "input"))
      (node (ref "IC7") (pin "2") (pinfunction "A_2") (pintype "input"))
    )
    (net (code "72") (name "F.1") (class "Default")
      (node (ref "FIELD") (pin "3") (pinfunction "QA_3") (pintype "output"))
      (node (ref "IC20") (pin "11") (pinfunction "A1_11") (pintype "input"))
      (node (ref "IC30") (pin "8") (pinfunction "A4_8") (pintype "input"))
      (node (ref "SV2") (pin "6") (pinfunction "6_6") (pintype "passive"))
    )
    (net (code "73") (name "F.2") (class "Default")
      (node (ref "FIELD") (pin "2") (pinfunction "QB_2") (pintype "output"))
      (node (ref "IC20") (pin "13") (pinfunction "A2_13") (pintype "input"))
      (node (ref "IC30") (pin "11") (pinfunction "A1_11") (pintype "input"))
      (node (ref "SV2") (pin "4") (pinfunction "4_4") (pintype "passive"))
    )
    (net (code "74") (name "F.3") (class "Default")
      (node (ref "FIELD") (pin "6") (pinfunction "QC_6") (pintype "output"))
      (node (ref "IC20") (pin "15") (pinfunction "A3_15") (pintype "input"))
      (node (ref "IC30") (pin "13") (pinfunction "A2_13") (pintype "input"))
      (node (ref "SV2") (pin "2") (pinfunction "2_2") (pintype "passive"))
    )
    (net (code "75") (name "GND") (class "Default")
      (node (ref "C1") (pin "2") (pinfunction "2_2") (pintype "passive"))
      (node (ref "C10") (pin "2") (pinfunction "2_2") (pintype "passive"))
      (node (ref "C11") (pin "2") (pinfunction "2_2") (pintype "passive"))
      (node (ref "C12") (pin "2") (pinfunction "2_2") (pintype "passive"))
      (node (ref "C13") (pin "2") (pinfunction "2_2") (pintype "passive"))
      (node (ref "C14") (pin "2") (pinfunction "2_2") (pintype "passive"))
      (node (ref "C15") (pin "2") (pinfunction "2_2") (pintype "passive"))
      (node (ref "C16") (pin "2") (pinfunction "2_2") (pintype "passive"))
      (node (ref "C17") (pin "2") (pinfunction "2_2") (pintype "passive"))
      (node (ref "C18") (pin "2") (pinfunction "2_2") (pintype "passive"))
      (node (ref "C19") (pin "2") (pinfunction "2_2") (pintype "passive"))
      (node (ref "C2") (pin "2") (pinfunction "2_2") (pintype "passive"))
      (node (ref "C20") (pin "2") (pinfunction "2_2") (pintype "passive"))
      (node (ref "C21") (pin "2") (pinfunction "2_2") (pintype "passive"))
      (node (ref "C22") (pin "2") (pinfunction "2_2") (pintype "passive"))
      (node (ref "C23") (pin "2") (pinfunction "2_2") (pintype "passive"))
      (node (ref "C24") (pin "2") (pinfunction "2_2") (pintype "passive"))
      (node (ref "C25") (pin "2") (pinfunction "2_2") (pintype "passive"))
      (node (ref "C26") (pin "2") (pinfunction "2_2") (pintype "passive"))
      (node (ref "C27") (pin "2") (pinfunction "2_2") (pintype "passive"))
      (node (ref "C28") (pin "2") (pinfunction "2_2") (pintype "passive"))
      (node (ref "C29") (pin "2") (pinfunction "2_2") (pintype "passive"))
      (node (ref "C3") (pin "2") (pinfunction "2_2") (pintype "passive"))
      (node (ref "C30") (pin "2") (pinfunction "2_2") (pintype "passive"))
      (node (ref "C31") (pin "2") (pinfunction "2_2") (pintype "passive"))
      (node (ref "C32") (pin "2") (pinfunction "2_2") (pintype "passive"))
      (node (ref "C33") (pin "2") (pinfunction "2_2") (pintype "passive"))
      (node (ref "C34") (pin "2") (pinfunction "2_2") (pintype "passive"))
      (node (ref "C35") (pin "2") (pinfunction "2_2") (pintype "passive"))
      (node (ref "C35L") (pin "1") (pinfunction "1_1") (pintype "passive"))
      (node (ref "C35L") (pin "11") (pinfunction "11_11") (pintype "passive"))
      (node (ref "C35L") (pin "13") (pinfunction "13_13") (pintype "passive"))
      (node (ref "C35L") (pin "15") (pinfunction "15_15") (pintype "passive"))
      (node (ref "C35L") (pin "17") (pinfunction "17_17") (pintype "passive"))
      (node (ref "C35L") (pin "19") (pinfunction "19_19") (pintype "passive"))
      (node (ref "C35L") (pin "21") (pinfunction "21_21") (pintype "passive"))
      (node (ref "C35L") (pin "23") (pinfunction "23_23") (pintype "passive"))
      (node (ref "C35L") (pin "25") (pinfunction "25_25") (pintype "passive"))
      (node (ref "C35L") (pin "27") (pinfunction "27_27") (pintype "passive"))
      (node (ref "C35L") (pin "29") (pinfunction "29_29") (pintype "passive"))
      (node (ref "C35L") (pin "3") (pinfunction "3_3") (pintype "passive"))
      (node (ref "C35L") (pin "31") (pinfunction "31_31") (pintype "passive"))
      (node (ref "C35L") (pin "33") (pinfunction "33_33") (pintype "passive"))
      (node (ref "C35L") (pin "35") (pinfunction "35_35") (pintype "passive"))
      (node (ref "C35L") (pin "37") (pinfunction "37_37") (pintype "passive"))
      (node (ref "C35L") (pin "39") (pinfunction "39_39") (pintype "passive"))
      (node (ref "C35L") (pin "5") (pinfunction "5_5") (pintype "passive"))
      (node (ref "C35L") (pin "7") (pinfunction "7_7") (pintype "passive"))
      (node (ref "C35L") (pin "9") (pinfunction "9_9") (pintype "passive"))
      (node (ref "C36") (pin "2") (pinfunction "2_2") (pintype "passive"))
      (node (ref "C36L") (pin "1") (pinfunction "1_1") (pintype "passive"))
      (node (ref "C36L") (pin "11") (pinfunction "11_11") (pintype "passive"))
      (node (ref "C36L") (pin "13") (pinfunction "13_13") (pintype "passive"))
      (node (ref "C36L") (pin "15") (pinfunction "15_15") (pintype "passive"))
      (node (ref "C36L") (pin "17") (pinfunction "17_17") (pintype "passive"))
      (node (ref "C36L") (pin "19") (pinfunction "19_19") (pintype "passive"))
      (node (ref "C36L") (pin "21") (pinfunction "21_21") (pintype "passive"))
      (node (ref "C36L") (pin "23") (pinfunction "23_23") (pintype "passive"))
      (node (ref "C36L") (pin "25") (pinfunction "25_25") (pintype "passive"))
      (node (ref "C36L") (pin "27") (pinfunction "27_27") (pintype "passive"))
      (node (ref "C36L") (pin "29") (pinfunction "29_29") (pintype "passive"))
      (node (ref "C36L") (pin "3") (pinfunction "3_3") (pintype "passive"))
      (node (ref "C36L") (pin "31") (pinfunction "31_31") (pintype "passive"))
      (node (ref "C36L") (pin "33") (pinfunction "33_33") (pintype "passive"))
      (node (ref "C36L") (pin "35") (pinfunction "35_35") (pintype "passive"))
      (node (ref "C36L") (pin "37") (pinfunction "37_37") (pintype "passive"))
      (node (ref "C36L") (pin "39") (pinfunction "39_39") (pintype "passive"))
      (node (ref "C36L") (pin "5") (pinfunction "5_5") (pintype "passive"))
      (node (ref "C36L") (pin "7") (pinfunction "7_7") (pintype "passive"))
      (node (ref "C36L") (pin "9") (pinfunction "9_9") (pintype "passive"))
      (node (ref "C37") (pin "2") (pinfunction "2_2") (pintype "passive"))
      (node (ref "C38") (pin "2") (pinfunction "2_2") (pintype "passive"))
      (node (ref "C39") (pin "2") (pinfunction "2_2") (pintype "passive"))
      (node (ref "C4") (pin "2") (pinfunction "2_2") (pintype "passive"))
      (node (ref "C40") (pin "2") (pinfunction "2_2") (pintype "passive"))
      (node (ref "C41") (pin "2") (pinfunction "2_2") (pintype "passive"))
      (node (ref "C42") (pin "2") (pinfunction "2_2") (pintype "passive"))
      (node (ref "C43") (pin "2") (pinfunction "2_2") (pintype "passive"))
      (node (ref "C44") (pin "2") (pinfunction "2_2") (pintype "passive"))
      (node (ref "C45") (pin "-") (pinfunction "-_-") (pintype "passive"))
      (node (ref "C46") (pin "2") (pinfunction "2_2") (pintype "passive"))
      (node (ref "C47") (pin "2") (pinfunction "2_2") (pintype "passive"))
      (node (ref "C5") (pin "2") (pinfunction "2_2") (pintype "passive"))
      (node (ref "C6") (pin "2") (pinfunction "2_2") (pintype "passive"))
      (node (ref "C7") (pin "2") (pinfunction "2_2") (pintype "passive"))
      (node (ref "C8") (pin "2") (pinfunction "2_2") (pintype "passive"))
      (node (ref "C9") (pin "2") (pinfunction "2_2") (pintype "passive"))
      (node (ref "D34L") (pin "1") (pinfunction "1_1") (pintype "passive"))
      (node (ref "D34L") (pin "11") (pinfunction "11_11") (pintype "passive"))
      (node (ref "D34L") (pin "13") (pinfunction "13_13") (pintype "passive"))
      (node (ref "D34L") (pin "15") (pinfunction "15_15") (pintype "passive"))
      (node (ref "D34L") (pin "17") (pinfunction "17_17") (pintype "passive"))
      (node (ref "D34L") (pin "19") (pinfunction "19_19") (pintype "passive"))
      (node (ref "D34L") (pin "21") (pinfunction "21_21") (pintype "passive"))
      (node (ref "D34L") (pin "23") (pinfunction "23_23") (pintype "passive"))
      (node (ref "D34L") (pin "25") (pinfunction "25_25") (pintype "passive"))
      (node (ref "D34L") (pin "27") (pinfunction "27_27") (pintype "passive"))
      (node (ref "D34L") (pin "29") (pinfunction "29_29") (pintype "passive"))
      (node (ref "D34L") (pin "3") (pinfunction "3_3") (pintype "passive"))
      (node (ref "D34L") (pin "31") (pinfunction "31_31") (pintype "passive"))
      (node (ref "D34L") (pin "33") (pinfunction "33_33") (pintype "passive"))
      (node (ref "D34L") (pin "35") (pinfunction "35_35") (pintype "passive"))
      (node (ref "D34L") (pin "37") (pinfunction "37_37") (pintype "passive"))
      (node (ref "D34L") (pin "39") (pinfunction "39_39") (pintype "passive"))
      (node (ref "D34L") (pin "5") (pinfunction "5_5") (pintype "passive"))
      (node (ref "D34L") (pin "7") (pinfunction "7_7") (pintype "passive"))
      (node (ref "D34L") (pin "9") (pinfunction "9_9") (pintype "passive"))
      (node (ref "D35L") (pin "1") (pinfunction "1_1") (pintype "passive"))
      (node (ref "D35L") (pin "11") (pinfunction "11_11") (pintype "passive"))
      (node (ref "D35L") (pin "13") (pinfunction "13_13") (pintype "passive"))
      (node (ref "D35L") (pin "15") (pinfunction "15_15") (pintype "passive"))
      (node (ref "D35L") (pin "17") (pinfunction "17_17") (pintype "passive"))
      (node (ref "D35L") (pin "19") (pinfunction "19_19") (pintype "passive"))
      (node (ref "D35L") (pin "21") (pinfunction "21_21") (pintype "passive"))
      (node (ref "D35L") (pin "23") (pinfunction "23_23") (pintype "passive"))
      (node (ref "D35L") (pin "25") (pinfunction "25_25") (pintype "passive"))
      (node (ref "D35L") (pin "27") (pinfunction "27_27") (pintype "passive"))
      (node (ref "D35L") (pin "29") (pinfunction "29_29") (pintype "passive"))
      (node (ref "D35L") (pin "3") (pinfunction "3_3") (pintype "passive"))
      (node (ref "D35L") (pin "31") (pinfunction "31_31") (pintype "passive"))
      (node (ref "D35L") (pin "33") (pinfunction "33_33") (pintype "passive"))
      (node (ref "D35L") (pin "35") (pinfunction "35_35") (pintype "passive"))
      (node (ref "D35L") (pin "37") (pinfunction "37_37") (pintype "passive"))
      (node (ref "D35L") (pin "39") (pinfunction "39_39") (pintype "passive"))
      (node (ref "D35L") (pin "5") (pinfunction "5_5") (pintype "passive"))
      (node (ref "D35L") (pin "7") (pinfunction "7_7") (pintype "passive"))
      (node (ref "D35L") (pin "9") (pinfunction "9_9") (pintype "passive"))
      (node (ref "D36L") (pin "1") (pinfunction "1_1") (pintype "passive"))
      (node (ref "D36L") (pin "11") (pinfunction "11_11") (pintype "passive"))
      (node (ref "D36L") (pin "13") (pinfunction "13_13") (pintype "passive"))
      (node (ref "D36L") (pin "15") (pinfunction "15_15") (pintype "passive"))
      (node (ref "D36L") (pin "17") (pinfunction "17_17") (pintype "passive"))
      (node (ref "D36L") (pin "19") (pinfunction "19_19") (pintype "passive"))
      (node (ref "D36L") (pin "21") (pinfunction "21_21") (pintype "passive"))
      (node (ref "D36L") (pin "23") (pinfunction "23_23") (pintype "passive"))
      (node (ref "D36L") (pin "25") (pinfunction "25_25") (pintype "passive"))
      (node (ref "D36L") (pin "27") (pinfunction "27_27") (pintype "passive"))
      (node (ref "D36L") (pin "29") (pinfunction "29_29") (pintype "passive"))
      (node (ref "D36L") (pin "3") (pinfunction "3_3") (pintype "passive"))
      (node (ref "D36L") (pin "31") (pinfunction "31_31") (pintype "passive"))
      (node (ref "D36L") (pin "33") (pinfunction "33_33") (pintype "passive"))
      (node (ref "D36L") (pin "35") (pinfunction "35_35") (pintype "passive"))
      (node (ref "D36L") (pin "37") (pinfunction "37_37") (pintype "passive"))
      (node (ref "D36L") (pin "39") (pinfunction "39_39") (pintype "passive"))
      (node (ref "D36L") (pin "5") (pinfunction "5_5") (pintype "passive"))
      (node (ref "D36L") (pin "7") (pinfunction "7_7") (pintype "passive"))
      (node (ref "D36L") (pin "9") (pinfunction "9_9") (pintype "passive"))
      (node (ref "DAR4-7") (pin "4") (pinfunction "DN_4") (pintype "input"))
      (node (ref "DAR8-11") (pin "4") (pinfunction "DN_4") (pintype "input"))
      (node (ref "DMA0-3") (pin "4") (pinfunction "DN_4") (pintype "input"))
      (node (ref "DMA4-7") (pin "4") (pinfunction "DN_4") (pintype "input"))
      (node (ref "DMA8-11") (pin "4") (pinfunction "DN_4") (pintype "input"))
      (node (ref "FIELD") (pin "4") (pinfunction "DN_4") (pintype "input"))
      (node (ref "FIELD") (pin "5") (pinfunction "UP_5") (pintype "input"))
      (node (ref "FIELD") (pin "9") (pinfunction "D_9") (pintype "input"))
      (node (ref "IC1") (pin "7") (pinfunction "G_7") (pintype "input"))
      (node (ref "IC10") (pin "12") (pinfunction "D_12") (pintype "input"))
      (node (ref "IC10") (pin "2") (pinfunction "D_2") (pintype "input"))
      (node (ref "IC13") (pin "1") (pinfunction "G_1") (pintype "input"))
      (node (ref "IC13") (pin "2") (pinfunction "H_2") (pintype "input"))
      (node (ref "IC14") (pin "1") (pinfunction "G_1") (pintype "input"))
      (node (ref "IC14") (pin "13") (pinfunction "F_13") (pintype "input"))
      (node (ref "IC14") (pin "2") (pinfunction "H_2") (pintype "input"))
      (node (ref "IC14") (pin "4") (pinfunction "OI_4") (pintype "input"))
      (node (ref "IC15") (pin "4") (pinfunction "OI_4") (pintype "input"))
      (node (ref "IC16") (pin "1") (pinfunction "G_1") (pintype "input"))
      (node (ref "IC16") (pin "15") (pinfunction "G_15") (pintype "input"))
      (node (ref "IC17") (pin "1") (pinfunction "G_1") (pintype "input"))
      (node (ref "IC17") (pin "15") (pinfunction "G_15") (pintype "input"))
      (node (ref "IC2") (pin "7") (pinfunction "G_7") (pintype "input"))
      (node (ref "IC20") (pin "17") (pinfunction "A4_17") (pintype "input"))
      (node (ref "IC23") (pin "2") (pinfunction "D_2") (pintype "input"))
      (node (ref "IC25") (pin "5") (pinfunction "G2B_5") (pintype "input"))
      (node (ref "IC29") (pin "5") (pinfunction "G2B_5") (pintype "input"))
      (node (ref "IC3") (pin "7") (pinfunction "G_7") (pintype "input"))
      (node (ref "IC30") (pin "6") (pinfunction "A3_6") (pintype "input"))
      (node (ref "IC32") (pin "5") (pinfunction "G2B_5") (pintype "input"))
      (node (ref "IC35") (pin "13") (pinfunction "A2_13") (pintype "input"))
      (node (ref "IC35") (pin "15") (pinfunction "A3_15") (pintype "input"))
      (node (ref "IC35") (pin "17") (pinfunction "A4_17") (pintype "input"))
      (node (ref "IC36") (pin "4") (pinfunction "G2A_4") (pintype "input"))
      (node (ref "IC36") (pin "5") (pinfunction "G2B_5") (pintype "input"))
      (node (ref "IC37") (pin "6") (pinfunction "A3_6") (pintype "input"))
      (node (ref "IC38") (pin "11") (pinfunction "A1_11") (pintype "input"))
      (node (ref "IC38") (pin "13") (pinfunction "A2_13") (pintype "input"))
      (node (ref "IC38") (pin "15") (pinfunction "A3_15") (pintype "input"))
      (node (ref "IC38") (pin "17") (pinfunction "A4_17") (pintype "input"))
      (node (ref "IC4") (pin "7") (pinfunction "G_7") (pintype "input"))
      (node (ref "IC7") (pin "1") (pinfunction "G_1") (pintype "input"))
      (node (ref "IC7") (pin "15") (pinfunction "G_15") (pintype "input"))
      (node (ref "IC8") (pin "1") (pinfunction "GND_1") (pintype "power_in"))
      (node (ref "IC9") (pin "12") (pinfunction "D_12") (pintype "input"))
      (node (ref "IC9") (pin "2") (pinfunction "D_2") (pintype "input"))
      (node (ref "INTENB") (pin "4") (pinfunction "DN_4") (pintype "input"))
      (node (ref "INTENB") (pin "5") (pinfunction "UP_5") (pintype "input"))
      (node (ref "INTENB") (pin "9") (pinfunction "D_9") (pintype "input"))
      (node (ref "J10") (pin "2") (pinfunction "2_2") (pintype "passive"))
      (node (ref "J11") (pin "2") (pinfunction "2_2") (pintype "passive"))
      (node (ref "J12") (pin "2") (pinfunction "2_2") (pintype "passive"))
      (node (ref "J13") (pin "2") (pinfunction "2_2") (pintype "passive"))
      (node (ref "J14") (pin "2") (pinfunction "2_2") (pintype "passive"))
      (node (ref "J2") (pin "2") (pinfunction "2_2") (pintype "passive"))
      (node (ref "J6") (pin "2") (pinfunction "2_2") (pintype "passive"))
      (node (ref "J8") (pin "2") (pinfunction "2_2") (pintype "passive"))
      (node (ref "J9") (pin "2") (pinfunction "2_2") (pintype "passive"))
      (node (ref "RS08") (pin "31") (pinfunction "31_31") (pintype "passive"))
      (node (ref "RS08") (pin "39") (pinfunction "39_39") (pintype "passive"))
      (node (ref "SV2") (pin "25") (pinfunction "25_25") (pintype "passive"))
      (node (ref "SV2") (pin "26") (pinfunction "26_26") (pintype "passive"))
    )
    (net (code "76") (name "NXD") (class "Default")
      (node (ref "IC23") (pin "5") (pinfunction "Q_5") (pintype "output"))
      (node (ref "IC30") (pin "4") (pinfunction "A2_4") (pintype "input"))
      (node (ref "SV1") (pin "17") (pinfunction "17_17") (pintype "passive"))
    )
    (net (code "77") (name "Net-(DAR4-7A-CLR)") (class "Default")
      (node (ref "DAR4-7") (pin "14") (pinfunction "CLR_14") (pintype "input"))
      (node (ref "DAR8-11") (pin "14") (pinfunction "CLR_14") (pintype "input"))
      (node (ref "IC18") (pin "8") (pinfunction "O_8") (pintype "output"))
    )
    (net (code "78") (name "Net-(DAR4-7A-UP)") (class "Default")
      (node (ref "DAR4-7") (pin "5") (pinfunction "UP_5") (pintype "input"))
      (node (ref "DAR8-11") (pin "12") (pinfunction "CO_12") (pintype "output"))
    )
    (net (code "79") (name "Net-(DAR8-11A-UP)") (class "Default")
      (node (ref "DAR8-11") (pin "5") (pinfunction "UP_5") (pintype "input"))
      (node (ref "DMA0-3") (pin "12") (pinfunction "CO_12") (pintype "output"))
    )
    (net (code "80") (name "Net-(DMA0-3A-CLR)") (class "Default")
      (node (ref "DMA0-3") (pin "14") (pinfunction "CLR_14") (pintype "input"))
      (node (ref "DMA4-7") (pin "14") (pinfunction "CLR_14") (pintype "input"))
      (node (ref "DMA8-11") (pin "14") (pinfunction "CLR_14") (pintype "input"))
      (node (ref "IC18") (pin "6") (pinfunction "O_6") (pintype "output"))
    )
    (net (code "81") (name "Net-(DMA0-3A-UP)") (class "Default")
      (node (ref "DMA0-3") (pin "5") (pinfunction "UP_5") (pintype "input"))
      (node (ref "DMA4-7") (pin "12") (pinfunction "CO_12") (pintype "output"))
    )
    (net (code "82") (name "Net-(DMA4-7A-UP)") (class "Default")
      (node (ref "DMA4-7") (pin "5") (pinfunction "UP_5") (pintype "input"))
      (node (ref "DMA8-11") (pin "12") (pinfunction "CO_12") (pintype "output"))
    )
    (net (code "83") (name "Net-(IC1A-D0)") (class "Default")
      (node (ref "IC1") (pin "4") (pinfunction "D0_4") (pintype "input"))
      (node (ref "SW1") (pin "16") (pinfunction "16_16") (pintype "passive"))
    )
    (net (code "84") (name "Net-(IC1A-D1)") (class "Default")
      (node (ref "IC1") (pin "3") (pinfunction "D1_3") (pintype "input"))
      (node (ref "SW1") (pin "15") (pinfunction "15_15") (pintype "passive"))
    )
    (net (code "85") (name "Net-(IC1A-D2)") (class "Default")
      (node (ref "IC1") (pin "2") (pinfunction "D2_2") (pintype "input"))
      (node (ref "SW1") (pin "14") (pinfunction "14_14") (pintype "passive"))
    )
    (net (code "86") (name "Net-(IC1A-D3)") (class "Default")
      (node (ref "IC1") (pin "1") (pinfunction "D3_1") (pintype "input"))
      (node (ref "SW1") (pin "13") (pinfunction "13_13") (pintype "passive"))
    )
    (net (code "87") (name "Net-(IC1A-D4)") (class "Default")
      (node (ref "IC1") (pin "15") (pinfunction "D4_15") (pintype "input"))
      (node (ref "SW1") (pin "12") (pinfunction "12_12") (pintype "passive"))
    )
    (net (code "88") (name "Net-(IC1A-D5)") (class "Default")
      (node (ref "IC1") (pin "14") (pinfunction "D5_14") (pintype "input"))
      (node (ref "SW1") (pin "11") (pinfunction "11_11") (pintype "passive"))
    )
    (net (code "89") (name "Net-(IC1A-D6)") (class "Default")
      (node (ref "IC1") (pin "13") (pinfunction "D6_13") (pintype "input"))
      (node (ref "SW1") (pin "10") (pinfunction "10_10") (pintype "passive"))
    )
    (net (code "90") (name "Net-(IC1A-D7)") (class "Default")
      (node (ref "IC1") (pin "12") (pinfunction "D7_12") (pintype "input"))
      (node (ref "SW1") (pin "9") (pinfunction "9_9") (pintype "passive"))
    )
    (net (code "91") (name "Net-(IC1A-Y)") (class "Default")
      (node (ref "IC1") (pin "5") (pinfunction "Y_5") (pintype "output"))
      (node (ref "IC5") (pin "1") (pinfunction "I0_1") (pintype "input"))
    )
    (net (code "92") (name "Net-(IC2A-D0)") (class "Default")
      (node (ref "IC2") (pin "4") (pinfunction "D0_4") (pintype "input"))
      (node (ref "SW2") (pin "16") (pinfunction "16_16") (pintype "passive"))
    )
    (net (code "93") (name "Net-(IC2A-D1)") (class "Default")
      (node (ref "IC2") (pin "3") (pinfunction "D1_3") (pintype "input"))
      (node (ref "SW2") (pin "15") (pinfunction "15_15") (pintype "passive"))
    )
    (net (code "94") (name "Net-(IC2A-D2)") (class "Default")
      (node (ref "IC2") (pin "2") (pinfunction "D2_2") (pintype "input"))
      (node (ref "SW2") (pin "14") (pinfunction "14_14") (pintype "passive"))
    )
    (net (code "95") (name "Net-(IC2A-D3)") (class "Default")
      (node (ref "IC2") (pin "1") (pinfunction "D3_1") (pintype "input"))
      (node (ref "SW2") (pin "13") (pinfunction "13_13") (pintype "passive"))
    )
    (net (code "96") (name "Net-(IC2A-D4)") (class "Default")
      (node (ref "IC2") (pin "15") (pinfunction "D4_15") (pintype "input"))
      (node (ref "SW2") (pin "12") (pinfunction "12_12") (pintype "passive"))
    )
    (net (code "97") (name "Net-(IC2A-D5)") (class "Default")
      (node (ref "IC2") (pin "14") (pinfunction "D5_14") (pintype "input"))
      (node (ref "SW2") (pin "11") (pinfunction "11_11") (pintype "passive"))
    )
    (net (code "98") (name "Net-(IC2A-D6)") (class "Default")
      (node (ref "IC2") (pin "13") (pinfunction "D6_13") (pintype "input"))
      (node (ref "SW2") (pin "10") (pinfunction "10_10") (pintype "passive"))
    )
    (net (code "99") (name "Net-(IC2A-D7)") (class "Default")
      (node (ref "IC2") (pin "12") (pinfunction "D7_12") (pintype "input"))
      (node (ref "SW2") (pin "9") (pinfunction "9_9") (pintype "passive"))
    )
    (net (code "100") (name "Net-(IC2A-Y)") (class "Default")
      (node (ref "IC2") (pin "5") (pinfunction "Y_5") (pintype "output"))
      (node (ref "IC5") (pin "2") (pinfunction "I1_2") (pintype "input"))
    )
    (net (code "101") (name "Net-(IC3A-D0)") (class "Default")
      (node (ref "IC3") (pin "4") (pinfunction "D0_4") (pintype "input"))
      (node (ref "SW3") (pin "16") (pinfunction "16_16") (pintype "passive"))
    )
    (net (code "102") (name "Net-(IC3A-D1)") (class "Default")
      (node (ref "IC3") (pin "3") (pinfunction "D1_3") (pintype "input"))
      (node (ref "SW3") (pin "15") (pinfunction "15_15") (pintype "passive"))
    )
    (net (code "103") (name "Net-(IC3A-D2)") (class "Default")
      (node (ref "IC3") (pin "2") (pinfunction "D2_2") (pintype "input"))
      (node (ref "SW3") (pin "14") (pinfunction "14_14") (pintype "passive"))
    )
    (net (code "104") (name "Net-(IC3A-D3)") (class "Default")
      (node (ref "IC3") (pin "1") (pinfunction "D3_1") (pintype "input"))
      (node (ref "SW3") (pin "13") (pinfunction "13_13") (pintype "passive"))
    )
    (net (code "105") (name "Net-(IC3A-D4)") (class "Default")
      (node (ref "IC3") (pin "15") (pinfunction "D4_15") (pintype "input"))
      (node (ref "SW3") (pin "12") (pinfunction "12_12") (pintype "passive"))
    )
    (net (code "106") (name "Net-(IC3A-D5)") (class "Default")
      (node (ref "IC3") (pin "14") (pinfunction "D5_14") (pintype "input"))
      (node (ref "SW3") (pin "11") (pinfunction "11_11") (pintype "passive"))
    )
    (net (code "107") (name "Net-(IC3A-D6)") (class "Default")
      (node (ref "IC3") (pin "13") (pinfunction "D6_13") (pintype "input"))
      (node (ref "SW3") (pin "10") (pinfunction "10_10") (pintype "passive"))
    )
    (net (code "108") (name "Net-(IC3A-D7)") (class "Default")
      (node (ref "IC3") (pin "12") (pinfunction "D7_12") (pintype "input"))
      (node (ref "SW3") (pin "9") (pinfunction "9_9") (pintype "passive"))
    )
    (net (code "109") (name "Net-(IC3A-Y)") (class "Default")
      (node (ref "IC3") (pin "5") (pinfunction "Y_5") (pintype "output"))
      (node (ref "IC5") (pin "4") (pinfunction "I2_4") (pintype "input"))
    )
    (net (code "110") (name "Net-(IC4A-D0)") (class "Default")
      (node (ref "IC4") (pin "4") (pinfunction "D0_4") (pintype "input"))
      (node (ref "SW4") (pin "16") (pinfunction "16_16") (pintype "passive"))
    )
    (net (code "111") (name "Net-(IC4A-D1)") (class "Default")
      (node (ref "IC4") (pin "3") (pinfunction "D1_3") (pintype "input"))
      (node (ref "SW4") (pin "15") (pinfunction "15_15") (pintype "passive"))
    )
    (net (code "112") (name "Net-(IC4A-D2)") (class "Default")
      (node (ref "IC4") (pin "2") (pinfunction "D2_2") (pintype "input"))
      (node (ref "SW4") (pin "14") (pinfunction "14_14") (pintype "passive"))
    )
    (net (code "113") (name "Net-(IC4A-D3)") (class "Default")
      (node (ref "IC4") (pin "1") (pinfunction "D3_1") (pintype "input"))
      (node (ref "SW4") (pin "13") (pinfunction "13_13") (pintype "passive"))
    )
    (net (code "114") (name "Net-(IC4A-D4)") (class "Default")
      (node (ref "IC4") (pin "15") (pinfunction "D4_15") (pintype "input"))
      (node (ref "SW4") (pin "12") (pinfunction "12_12") (pintype "passive"))
    )
    (net (code "115") (name "Net-(IC4A-D5)") (class "Default")
      (node (ref "IC4") (pin "14") (pinfunction "D5_14") (pintype "input"))
      (node (ref "SW4") (pin "11") (pinfunction "11_11") (pintype "passive"))
    )
    (net (code "116") (name "Net-(IC4A-D6)") (class "Default")
      (node (ref "IC4") (pin "13") (pinfunction "D6_13") (pintype "input"))
      (node (ref "SW4") (pin "10") (pinfunction "10_10") (pintype "passive"))
    )
    (net (code "117") (name "Net-(IC4A-D7)") (class "Default")
      (node (ref "IC4") (pin "12") (pinfunction "D7_12") (pintype "input"))
      (node (ref "SW4") (pin "9") (pinfunction "9_9") (pintype "passive"))
    )
    (net (code "118") (name "Net-(IC4A-Y)") (class "Default")
      (node (ref "IC4") (pin "5") (pinfunction "Y_5") (pintype "output"))
      (node (ref "IC5") (pin "5") (pinfunction "I3_5") (pintype "input"))
    )
    (net (code "119") (name "Net-(IC8-CV)") (class "Default")
      (node (ref "C48") (pin "2") (pinfunction "2_2") (pintype "passive"))
      (node (ref "IC8") (pin "5") (pinfunction "CV_5") (pintype "input"))
    )
    (net (code "120") (name "Net-(IC8-DIS)") (class "Default")
      (node (ref "IC8") (pin "7") (pinfunction "DIS_7") (pintype "input"))
      (node (ref "RA") (pin "2") (pinfunction "2_2") (pintype "passive"))
      (node (ref "RB") (pin "1") (pinfunction "1_1") (pintype "passive"))
    )
    (net (code "121") (name "Net-(IC8-THR)") (class "Default")
      (node (ref "C47") (pin "1") (pinfunction "1_1") (pintype "passive"))
      (node (ref "IC8") (pin "2") (pinfunction "TR_2") (pintype "input"))
      (node (ref "IC8") (pin "6") (pinfunction "THR_6") (pintype "input"))
      (node (ref "RB") (pin "2") (pinfunction "2_2") (pintype "passive"))
    )
    (net (code "122") (name "Net-(IC10B-PRE)") (class "Default")
      (node (ref "IC10") (pin "10") (pinfunction "PRE_10") (pintype "input"))
      (node (ref "IC18") (pin "11") (pinfunction "O_11") (pintype "output"))
    )
    (net (code "123") (name "Net-(IC10B-~{Q})") (class "Default")
      (node (ref "IC10") (pin "8") (pinfunction "~{Q}_8") (pintype "output"))
      (node (ref "IC11") (pin "11") (pinfunction "CLK_11") (pintype "input"))
    )
    (net (code "124") (name "Net-(IC12A-I0)") (class "Default")
      (node (ref "IC12") (pin "1") (pinfunction "I0_1") (pintype "input"))
      (node (ref "IC12") (pin "2") (pinfunction "I1_2") (pintype "input"))
      (node (ref "IC8") (pin "3") (pinfunction "Q_3") (pintype "output"))
      (node (ref "RL") (pin "2") (pinfunction "2_2") (pintype "passive"))
    )
    (net (code "125") (name "Net-(IC12B-I1)") (class "Default")
      (node (ref "IC12") (pin "5") (pinfunction "I1_5") (pintype "input"))
      (node (ref "IC12") (pin "8") (pinfunction "O_8") (pintype "output"))
    )
    (net (code "126") (name "Net-(IC12C-I0)") (class "Default")
      (node (ref "IC12") (pin "10") (pinfunction "I1_10") (pintype "input"))
      (node (ref "IC12") (pin "11") (pinfunction "O_11") (pintype "output"))
      (node (ref "IC12") (pin "9") (pinfunction "I0_9") (pintype "input"))
    )
    (net (code "127") (name "Net-(IC13A-A)") (class "Default")
      (node (ref "IC13") (pin "8") (pinfunction "A_8") (pintype "input"))
      (node (ref "IC14") (pin "8") (pinfunction "A_8") (pintype "input"))
      (node (ref "IC15") (pin "6") (pinfunction "ODD_6") (pintype "output"))
    )
    (net (code "128") (name "Net-(IC16B-Y1)") (class "Default")
      (node (ref "IC16") (pin "11") (pinfunction "Y1_11") (pintype "output"))
      (node (ref "IC22") (pin "1") (pinfunction "I_1") (pintype "input"))
    )
    (net (code "129") (name "Net-(IC17A-Y0)") (class "Default")
      (node (ref "IC17") (pin "4") (pinfunction "Y0_4") (pintype "output"))
      (node (ref "IC22") (pin "11") (pinfunction "I_11") (pintype "input"))
    )
    (net (code "130") (name "Net-(IC19A-I)") (class "Default")
      (node (ref "IC19") (pin "1") (pinfunction "I_1") (pintype "input"))
      (node (ref "IC7") (pin "5") (pinfunction "Y1_5") (pintype "output"))
    )
    (net (code "131") (name "Net-(IC19E-I)") (class "Default")
      (node (ref "IC19") (pin "11") (pinfunction "I_11") (pintype "input"))
      (node (ref "IC7") (pin "12") (pinfunction "Y0_12") (pintype "output"))
    )
    (net (code "132") (name "Net-(IC21A-Y0)") (class "Default")
      (node (ref "IC21") (pin "4") (pinfunction "Y0_4") (pintype "output"))
      (node (ref "SW1") (pin "1") (pinfunction "1_1") (pintype "passive"))
      (node (ref "SW1") (pin "2") (pinfunction "2_2") (pintype "passive"))
      (node (ref "SW1") (pin "3") (pinfunction "3_3") (pintype "passive"))
      (node (ref "SW1") (pin "4") (pinfunction "4_4") (pintype "passive"))
      (node (ref "SW1") (pin "5") (pinfunction "5_5") (pintype "passive"))
      (node (ref "SW1") (pin "6") (pinfunction "6_6") (pintype "passive"))
      (node (ref "SW1") (pin "7") (pinfunction "7_7") (pintype "passive"))
      (node (ref "SW1") (pin "8") (pinfunction "8_8") (pintype "passive"))
    )
    (net (code "133") (name "Net-(IC21A-Y1)") (class "Default")
      (node (ref "IC21") (pin "5") (pinfunction "Y1_5") (pintype "output"))
      (node (ref "SW2") (pin "1") (pinfunction "1_1") (pintype "passive"))
      (node (ref "SW2") (pin "2") (pinfunction "2_2") (pintype "passive"))
      (node (ref "SW2") (pin "3") (pinfunction "3_3") (pintype "passive"))
      (node (ref "SW2") (pin "4") (pinfunction "4_4") (pintype "passive"))
      (node (ref "SW2") (pin "5") (pinfunction "5_5") (pintype "passive"))
      (node (ref "SW2") (pin "6") (pinfunction "6_6") (pintype "passive"))
      (node (ref "SW2") (pin "7") (pinfunction "7_7") (pintype "passive"))
      (node (ref "SW2") (pin "8") (pinfunction "8_8") (pintype "passive"))
    )
    (net (code "134") (name "Net-(IC21A-Y2)") (class "Default")
      (node (ref "IC21") (pin "6") (pinfunction "Y2_6") (pintype "output"))
      (node (ref "SW3") (pin "1") (pinfunction "1_1") (pintype "passive"))
      (node (ref "SW3") (pin "2") (pinfunction "2_2") (pintype "passive"))
      (node (ref "SW3") (pin "3") (pinfunction "3_3") (pintype "passive"))
      (node (ref "SW3") (pin "4") (pinfunction "4_4") (pintype "passive"))
      (node (ref "SW3") (pin "5") (pinfunction "5_5") (pintype "passive"))
      (node (ref "SW3") (pin "6") (pinfunction "6_6") (pintype "passive"))
      (node (ref "SW3") (pin "7") (pinfunction "7_7") (pintype "passive"))
      (node (ref "SW3") (pin "8") (pinfunction "8_8") (pintype "passive"))
    )
    (net (code "135") (name "Net-(IC21A-Y3)") (class "Default")
      (node (ref "IC21") (pin "7") (pinfunction "Y3_7") (pintype "output"))
      (node (ref "SW4") (pin "1") (pinfunction "1_1") (pintype "passive"))
      (node (ref "SW4") (pin "2") (pinfunction "2_2") (pintype "passive"))
      (node (ref "SW4") (pin "3") (pinfunction "3_3") (pintype "passive"))
      (node (ref "SW4") (pin "4") (pinfunction "4_4") (pintype "passive"))
      (node (ref "SW4") (pin "5") (pinfunction "5_5") (pintype "passive"))
      (node (ref "SW4") (pin "6") (pinfunction "6_6") (pintype "passive"))
      (node (ref "SW4") (pin "7") (pinfunction "7_7") (pintype "passive"))
      (node (ref "SW4") (pin "8") (pinfunction "8_8") (pintype "passive"))
    )
    (net (code "136") (name "Net-(IC36A-Y0)") (class "Default")
      (node (ref "IC36") (pin "15") (pinfunction "Y0_15") (pintype "output"))
      (node (ref "PAD2") (pin "1") (pinfunction "P_1") (pintype "passive"))
    )
    (net (code "137") (name "Net-(IC36A-Y1)") (class "Default")
      (node (ref "IC36") (pin "14") (pinfunction "Y1_14") (pintype "output"))
      (node (ref "PAD3") (pin "1") (pinfunction "P_1") (pintype "passive"))
    )
    (net (code "138") (name "Net-(IC36A-Y2)") (class "Default")
      (node (ref "IC36") (pin "13") (pinfunction "Y2_13") (pintype "output"))
      (node (ref "PAD4") (pin "1") (pinfunction "P_1") (pintype "passive"))
    )
    (net (code "139") (name "Net-(IC36A-Y3)") (class "Default")
      (node (ref "IC36") (pin "12") (pinfunction "Y3_12") (pintype "output"))
      (node (ref "PAD5") (pin "1") (pinfunction "P_1") (pintype "passive"))
    )
    (net (code "140") (name "Net-(IC36A-Y4)") (class "Default")
      (node (ref "IC36") (pin "11") (pinfunction "Y4_11") (pintype "output"))
      (node (ref "PAD6") (pin "1") (pinfunction "P_1") (pintype "passive"))
    )
    (net (code "141") (name "Net-(IC36A-Y5)") (class "Default")
      (node (ref "IC36") (pin "10") (pinfunction "Y5_10") (pintype "output"))
      (node (ref "PAD7") (pin "1") (pinfunction "P_1") (pintype "passive"))
    )
    (net (code "142") (name "Net-(IC36A-Y6)") (class "Default")
      (node (ref "IC36") (pin "9") (pinfunction "Y6_9") (pintype "output"))
      (node (ref "PAD8") (pin "1") (pinfunction "P_1") (pintype "passive"))
    )
    (net (code "143") (name "Net-(IC36A-Y7)") (class "Default")
      (node (ref "IC36") (pin "7") (pinfunction "Y7_7") (pintype "output"))
      (node (ref "PAD9") (pin "1") (pinfunction "P_1") (pintype "passive"))
    )
    (net (code "144") (name "PBIT") (class "Default")
      (node (ref "IC14") (pin "6") (pinfunction "ODD_6") (pintype "output"))
      (node (ref "IC35") (pin "11") (pinfunction "A1_11") (pintype "input"))
    )
    (net (code "145") (name "PCA") (class "Default")
      (node (ref "IC12") (pin "3") (pinfunction "O_3") (pintype "output"))
      (node (ref "IC37") (pin "8") (pinfunction "A4_8") (pintype "input"))
      (node (ref "IC55") (pin "5") (pinfunction "I1_5") (pintype "input"))
    )
    (net (code "146") (name "PER") (class "Default")
      (node (ref "IC30") (pin "2") (pinfunction "A1_2") (pintype "input"))
      (node (ref "IC9") (pin "9") (pinfunction "Q_9") (pintype "output"))
      (node (ref "SV1") (pin "21") (pinfunction "21_21") (pintype "passive"))
    )
    (net (code "147") (name "PIE") (class "Default")
      (node (ref "IC30") (pin "17") (pinfunction "A4_17") (pintype "input"))
      (node (ref "IC55") (pin "4") (pinfunction "I0_4") (pintype "input"))
      (node (ref "INTENB") (pin "2") (pinfunction "QB_2") (pintype "output"))
      (node (ref "SV1") (pin "5") (pinfunction "5_5") (pintype "passive"))
    )
    (net (code "148") (name "PROTECT") (class "Default")
      (node (ref "IC5") (pin "6") (pinfunction "O_6") (pintype "output"))
      (node (ref "IC6") (pin "3") (pinfunction "B_3") (pintype "input"))
    )
    (net (code "149") (name "VCC") (class "Default")
      (node (ref "C1") (pin "1") (pinfunction "1_1") (pintype "passive"))
      (node (ref "C10") (pin "1") (pinfunction "1_1") (pintype "passive"))
      (node (ref "C11") (pin "1") (pinfunction "1_1") (pintype "passive"))
      (node (ref "C12") (pin "1") (pinfunction "1_1") (pintype "passive"))
      (node (ref "C13") (pin "1") (pinfunction "1_1") (pintype "passive"))
      (node (ref "C14") (pin "1") (pinfunction "1_1") (pintype "passive"))
      (node (ref "C15") (pin "1") (pinfunction "1_1") (pintype "passive"))
      (node (ref "C16") (pin "1") (pinfunction "1_1") (pintype "passive"))
      (node (ref "C17") (pin "1") (pinfunction "1_1") (pintype "passive"))
      (node (ref "C18") (pin "1") (pinfunction "1_1") (pintype "passive"))
      (node (ref "C19") (pin "1") (pinfunction "1_1") (pintype "passive"))
      (node (ref "C2") (pin "1") (pinfunction "1_1") (pintype "passive"))
      (node (ref "C20") (pin "1") (pinfunction "1_1") (pintype "passive"))
      (node (ref "C21") (pin "1") (pinfunction "1_1") (pintype "passive"))
      (node (ref "C22") (pin "1") (pinfunction "1_1") (pintype "passive"))
      (node (ref "C23") (pin "1") (pinfunction "1_1") (pintype "passive"))
      (node (ref "C24") (pin "1") (pinfunction "1_1") (pintype "passive"))
      (node (ref "C25") (pin "1") (pinfunction "1_1") (pintype "passive"))
      (node (ref "C26") (pin "1") (pinfunction "1_1") (pintype "passive"))
      (node (ref "C27") (pin "1") (pinfunction "1_1") (pintype "passive"))
      (node (ref "C28") (pin "1") (pinfunction "1_1") (pintype "passive"))
      (node (ref "C29") (pin "1") (pinfunction "1_1") (pintype "passive"))
      (node (ref "C3") (pin "1") (pinfunction "1_1") (pintype "passive"))
      (node (ref "C30") (pin "1") (pinfunction "1_1") (pintype "passive"))
      (node (ref "C31") (pin "1") (pinfunction "1_1") (pintype "passive"))
      (node (ref "C32") (pin "1") (pinfunction "1_1") (pintype "passive"))
      (node (ref "C33") (pin "1") (pinfunction "1_1") (pintype "passive"))
      (node (ref "C34") (pin "1") (pinfunction "1_1") (pintype "passive"))
      (node (ref "C35") (pin "1") (pinfunction "1_1") (pintype "passive"))
      (node (ref "C36") (pin "1") (pinfunction "1_1") (pintype "passive"))
      (node (ref "C37") (pin "1") (pinfunction "1_1") (pintype "passive"))
      (node (ref "C38") (pin "1") (pinfunction "1_1") (pintype "passive"))
      (node (ref "C39") (pin "1") (pinfunction "1_1") (pintype "passive"))
      (node (ref "C4") (pin "1") (pinfunction "1_1") (pintype "passive"))
      (node (ref "C40") (pin "1") (pinfunction "1_1") (pintype "passive"))
      (node (ref "C41") (pin "1") (pinfunction "1_1") (pintype "passive"))
      (node (ref "C42") (pin "1") (pinfunction "1_1") (pintype "passive"))
      (node (ref "C43") (pin "1") (pinfunction "1_1") (pintype "passive"))
      (node (ref "C44") (pin "1") (pinfunction "1_1") (pintype "passive"))
      (node (ref "C45") (pin "+") (pinfunction "+_+") (pintype "passive"))
      (node (ref "C46") (pin "1") (pinfunction "1_1") (pintype "passive"))
      (node (ref "C48") (pin "1") (pinfunction "1_1") (pintype "passive"))
      (node (ref "C5") (pin "1") (pinfunction "1_1") (pintype "passive"))
      (node (ref "C6") (pin "1") (pinfunction "1_1") (pintype "passive"))
      (node (ref "C7") (pin "1") (pinfunction "1_1") (pintype "passive"))
      (node (ref "C8") (pin "1") (pinfunction "1_1") (pintype "passive"))
      (node (ref "C9") (pin "1") (pinfunction "1_1") (pintype "passive"))
      (node (ref "IC11") (pin "10") (pinfunction "PRE_10") (pintype "input"))
      (node (ref "IC11") (pin "4") (pinfunction "PRE_4") (pintype "input"))
      (node (ref "IC13") (pin "3") (pinfunction "EI_3") (pintype "input"))
      (node (ref "IC14") (pin "3") (pinfunction "EI_3") (pintype "input"))
      (node (ref "IC15") (pin "3") (pinfunction "EI_3") (pintype "input"))
      (node (ref "IC36") (pin "6") (pinfunction "G1_6") (pintype "input"))
      (node (ref "IC8") (pin "4") (pinfunction "R_4") (pintype "input"))
      (node (ref "IC8") (pin "8") (pinfunction "V+_8") (pintype "power_in"))
      (node (ref "J3") (pin "2") (pinfunction "2_2") (pintype "passive"))
      (node (ref "J4") (pin "2") (pinfunction "2_2") (pintype "passive"))
      (node (ref "J5") (pin "2") (pinfunction "2_2") (pintype "passive"))
      (node (ref "J7") (pin "2") (pinfunction "2_2") (pintype "passive"))
      (node (ref "R1") (pin "2") (pinfunction "2_2") (pintype "passive"))
      (node (ref "R2") (pin "2") (pinfunction "2_2") (pintype "passive"))
      (node (ref "RA") (pin "1") (pinfunction "1_1") (pintype "passive"))
      (node (ref "RL") (pin "1") (pinfunction "1_1") (pintype "passive"))
      (node (ref "RS08") (pin "2") (pinfunction "2_2") (pintype "passive"))
      (node (ref "SV1") (pin "25") (pinfunction "25_25") (pintype "passive"))
      (node (ref "SV1") (pin "26") (pinfunction "26_26") (pintype "passive"))
    )
    (net (code "150") (name "WLS") (class "Default")
      (node (ref "IC37") (pin "4") (pinfunction "A2_4") (pintype "input"))
      (node (ref "IC9") (pin "5") (pinfunction "Q_5") (pintype "output"))
      (node (ref "SV1") (pin "15") (pinfunction "15_15") (pintype "passive"))
    )
    (net (code "151") (name "WRITING") (class "Default")
      (node (ref "IC10") (pin "5") (pinfunction "Q_5") (pintype "output"))
      (node (ref "IC41") (pin "13") (pinfunction "B_13") (pintype "input"))
      (node (ref "IC41") (pin "14") (pinfunction "A_14") (pintype "input"))
      (node (ref "IC6") (pin "2") (pinfunction "A_2") (pintype "input"))
      (node (ref "RS08") (pin "18") (pinfunction "18_18") (pintype "passive"))
      (node (ref "SV1") (pin "9") (pinfunction "9_9") (pintype "passive"))
    )
    (net (code "152") (name "unconnected-(C35L-Pad20)") (class "Default")
      (node (ref "C35L") (pin "20") (pinfunction "20_20") (pintype "passive"))
    )
    (net (code "153") (name "unconnected-(C35L-Pad40)") (class "Default")
      (node (ref "C35L") (pin "40") (pinfunction "40_40") (pintype "passive"))
    )
    (net (code "154") (name "unconnected-(C36L-Pad20)") (class "Default")
      (node (ref "C36L") (pin "20") (pinfunction "20_20") (pintype "passive"))
    )
    (net (code "155") (name "unconnected-(C36L-Pad40)") (class "Default")
      (node (ref "C36L") (pin "40") (pinfunction "40_40") (pintype "passive"))
    )
    (net (code "156") (name "unconnected-(D34L-Pad20)") (class "Default")
      (node (ref "D34L") (pin "20") (pinfunction "20_20") (pintype "passive"))
    )
    (net (code "157") (name "unconnected-(D34L-Pad36)") (class "Default")
      (node (ref "D34L") (pin "36") (pinfunction "36_36") (pintype "passive"))
    )
    (net (code "158") (name "unconnected-(D34L-Pad38)") (class "Default")
      (node (ref "D34L") (pin "38") (pinfunction "38_38") (pintype "passive"))
    )
    (net (code "159") (name "unconnected-(D34L-Pad40)") (class "Default")
      (node (ref "D34L") (pin "40") (pinfunction "40_40") (pintype "passive"))
    )
    (net (code "160") (name "unconnected-(D35L-Pad20)") (class "Default")
      (node (ref "D35L") (pin "20") (pinfunction "20_20") (pintype "passive"))
    )
    (net (code "161") (name "unconnected-(D35L-Pad40)") (class "Default")
      (node (ref "D35L") (pin "40") (pinfunction "40_40") (pintype "passive"))
    )
    (net (code "162") (name "unconnected-(D36L-Pad20)") (class "Default")
      (node (ref "D36L") (pin "20") (pinfunction "20_20") (pintype "passive"))
    )
    (net (code "163") (name "unconnected-(D36L-Pad40)") (class "Default")
      (node (ref "D36L") (pin "40") (pinfunction "40_40") (pintype "passive"))
    )
    (net (code "164") (name "unconnected-(DAR4-7A-BO-Pad13)") (class "Default")
      (node (ref "DAR4-7") (pin "13") (pinfunction "BO_13") (pintype "output"))
    )
    (net (code "165") (name "unconnected-(DAR4-7A-CO-Pad12)") (class "Default")
      (node (ref "DAR4-7") (pin "12") (pinfunction "CO_12") (pintype "output"))
    )
    (net (code "166") (name "unconnected-(DAR8-11A-BO-Pad13)") (class "Default")
      (node (ref "DAR8-11") (pin "13") (pinfunction "BO_13") (pintype "output"))
    )
    (net (code "167") (name "unconnected-(DMA0-3A-BO-Pad13)") (class "Default")
      (node (ref "DMA0-3") (pin "13") (pinfunction "BO_13") (pintype "output"))
    )
    (net (code "168") (name "unconnected-(DMA4-7A-BO-Pad13)") (class "Default")
      (node (ref "DMA4-7") (pin "13") (pinfunction "BO_13") (pintype "output"))
    )
    (net (code "169") (name "unconnected-(DMA8-11A-BO-Pad13)") (class "Default")
      (node (ref "DMA8-11") (pin "13") (pinfunction "BO_13") (pintype "output"))
    )
    (net (code "170") (name "unconnected-(FIELDA-BO-Pad13)") (class "Default")
      (node (ref "FIELD") (pin "13") (pinfunction "BO_13") (pintype "output"))
    )
    (net (code "171") (name "unconnected-(FIELDA-CO-Pad12)") (class "Default")
      (node (ref "FIELD") (pin "12") (pinfunction "CO_12") (pintype "output"))
    )
    (net (code "172") (name "unconnected-(FIELDA-QD-Pad7)") (class "Default")
      (node (ref "FIELD") (pin "7") (pinfunction "QD_7") (pintype "output"))
    )
    (net (code "173") (name "unconnected-(IC1A-W-Pad6)") (class "Default")
      (node (ref "IC1") (pin "6") (pinfunction "W_6") (pintype "output"))
    )
    (net (code "174") (name "unconnected-(IC2A-W-Pad6)") (class "Default")
      (node (ref "IC2") (pin "6") (pinfunction "W_6") (pintype "output"))
    )
    (net (code "175") (name "unconnected-(IC3A-W-Pad6)") (class "Default")
      (node (ref "IC3") (pin "6") (pinfunction "W_6") (pintype "output"))
    )
    (net (code "176") (name "unconnected-(IC4A-W-Pad6)") (class "Default")
      (node (ref "IC4") (pin "6") (pinfunction "W_6") (pintype "output"))
    )
    (net (code "177") (name "unconnected-(IC6A-Y0-Pad4)") (class "Default")
      (node (ref "IC6") (pin "4") (pinfunction "Y0_4") (pintype "output"))
    )
    (net (code "178") (name "unconnected-(IC6A-Y2-Pad6)") (class "Default")
      (node (ref "IC6") (pin "6") (pinfunction "Y2_6") (pintype "output"))
    )
    (net (code "179") (name "unconnected-(IC7A-Y0-Pad4)") (class "Default")
      (node (ref "IC7") (pin "4") (pinfunction "Y0_4") (pintype "output"))
    )
    (net (code "180") (name "unconnected-(IC7A-Y2-Pad6)") (class "Default")
      (node (ref "IC7") (pin "6") (pinfunction "Y2_6") (pintype "output"))
    )
    (net (code "181") (name "unconnected-(IC7A-Y3-Pad7)") (class "Default")
      (node (ref "IC7") (pin "7") (pinfunction "Y3_7") (pintype "output"))
    )
    (net (code "182") (name "unconnected-(IC7B-Y1-Pad11)") (class "Default")
      (node (ref "IC7") (pin "11") (pinfunction "Y1_11") (pintype "output"))
    )
    (net (code "183") (name "unconnected-(IC7B-Y2-Pad10)") (class "Default")
      (node (ref "IC7") (pin "10") (pinfunction "Y2_10") (pintype "output"))
    )
    (net (code "184") (name "unconnected-(IC7B-Y3-Pad9)") (class "Default")
      (node (ref "IC7") (pin "9") (pinfunction "Y3_9") (pintype "output"))
    )
    (net (code "185") (name "unconnected-(IC10A-~{Q}-Pad6)") (class "Default")
      (node (ref "IC10") (pin "6") (pinfunction "~{Q}_6") (pintype "output"))
    )
    (net (code "186") (name "unconnected-(IC11A-Q-Pad5)") (class "Default")
      (node (ref "IC11") (pin "5") (pinfunction "Q_5") (pintype "output"))
    )
    (net (code "187") (name "unconnected-(IC11B-~{Q}-Pad8)") (class "Default")
      (node (ref "IC11") (pin "8") (pinfunction "~{Q}_8") (pintype "output"))
    )
    (net (code "188") (name "unconnected-(IC13A-ODD-Pad6)") (class "Default")
      (node (ref "IC13") (pin "6") (pinfunction "ODD_6") (pintype "output"))
    )
    (net (code "189") (name "unconnected-(IC14A-EVN-Pad5)") (class "Default")
      (node (ref "IC14") (pin "5") (pinfunction "EVN_5") (pintype "output"))
    )
    (net (code "190") (name "unconnected-(IC15A-EVN-Pad5)") (class "Default")
      (node (ref "IC15") (pin "5") (pinfunction "EVN_5") (pintype "output"))
    )
    (net (code "191") (name "unconnected-(IC16A-Y1-Pad5)") (class "Default")
      (node (ref "IC16") (pin "5") (pinfunction "Y1_5") (pintype "output"))
    )
    (net (code "192") (name "unconnected-(IC16A-Y2-Pad6)") (class "Default")
      (node (ref "IC16") (pin "6") (pinfunction "Y2_6") (pintype "output"))
    )
    (net (code "193") (name "unconnected-(IC16A-Y3-Pad7)") (class "Default")
      (node (ref "IC16") (pin "7") (pinfunction "Y3_7") (pintype "output"))
    )
    (net (code "194") (name "unconnected-(IC16B-Y2-Pad10)") (class "Default")
      (node (ref "IC16") (pin "10") (pinfunction "Y2_10") (pintype "output"))
    )
    (net (code "195") (name "unconnected-(IC16B-Y3-Pad9)") (class "Default")
      (node (ref "IC16") (pin "9") (pinfunction "Y3_9") (pintype "output"))
    )
    (net (code "196") (name "unconnected-(IC17A-Y1-Pad5)") (class "Default")
      (node (ref "IC17") (pin "5") (pinfunction "Y1_5") (pintype "output"))
    )
    (net (code "197") (name "unconnected-(IC17A-Y2-Pad6)") (class "Default")
      (node (ref "IC17") (pin "6") (pinfunction "Y2_6") (pintype "output"))
    )
    (net (code "198") (name "unconnected-(IC17A-Y3-Pad7)") (class "Default")
      (node (ref "IC17") (pin "7") (pinfunction "Y3_7") (pintype "output"))
    )
    (net (code "199") (name "unconnected-(IC17B-Y2-Pad10)") (class "Default")
      (node (ref "IC17") (pin "10") (pinfunction "Y2_10") (pintype "output"))
    )
    (net (code "200") (name "unconnected-(IC17B-Y3-Pad9)") (class "Default")
      (node (ref "IC17") (pin "9") (pinfunction "Y3_9") (pintype "output"))
    )
    (net (code "201") (name "unconnected-(IC20B-Y4-Pad3)") (class "Default")
      (node (ref "IC20") (pin "3") (pinfunction "Y4_3") (pintype "tri_state"))
    )
    (net (code "202") (name "unconnected-(IC21B-Y0-Pad12)") (class "Default")
      (node (ref "IC21") (pin "12") (pinfunction "Y0_12") (pintype "output"))
    )
    (net (code "203") (name "unconnected-(IC21B-Y1-Pad11)") (class "Default")
      (node (ref "IC21") (pin "11") (pinfunction "Y1_11") (pintype "output"))
    )
    (net (code "204") (name "unconnected-(IC21B-Y2-Pad10)") (class "Default")
      (node (ref "IC21") (pin "10") (pinfunction "Y2_10") (pintype "output"))
    )
    (net (code "205") (name "unconnected-(IC25A-Y3-Pad12)") (class "Default")
      (node (ref "IC25") (pin "12") (pinfunction "Y3_12") (pintype "output"))
    )
    (net (code "206") (name "unconnected-(IC25A-Y5-Pad10)") (class "Default")
      (node (ref "IC25") (pin "10") (pinfunction "Y5_10") (pintype "output"))
    )
    (net (code "207") (name "unconnected-(IC25A-Y6-Pad9)") (class "Default")
      (node (ref "IC25") (pin "9") (pinfunction "Y6_9") (pintype "output"))
    )
    (net (code "208") (name "unconnected-(IC25A-Y7-Pad7)") (class "Default")
      (node (ref "IC25") (pin "7") (pinfunction "Y7_7") (pintype "output"))
    )
    (net (code "209") (name "unconnected-(IC27-Pad1)") (class "Default")
      (node (ref "IC27") (pin "1") (pinfunction "1_1") (pintype "passive"))
    )
    (net (code "210") (name "unconnected-(IC27-Pad2)") (class "Default")
      (node (ref "IC27") (pin "2") (pinfunction "2_2") (pintype "passive"))
    )
    (net (code "211") (name "unconnected-(IC27-Pad3)") (class "Default")
      (node (ref "IC27") (pin "3") (pinfunction "3_3") (pintype "passive"))
    )
    (net (code "212") (name "unconnected-(IC27-Pad4)") (class "Default")
      (node (ref "IC27") (pin "4") (pinfunction "4_4") (pintype "passive"))
    )
    (net (code "213") (name "unconnected-(IC27-Pad5)") (class "Default")
      (node (ref "IC27") (pin "5") (pinfunction "5_5") (pintype "passive"))
    )
    (net (code "214") (name "unconnected-(IC27-Pad6)") (class "Default")
      (node (ref "IC27") (pin "6") (pinfunction "6_6") (pintype "passive"))
    )
    (net (code "215") (name "unconnected-(IC27-Pad7)") (class "Default")
      (node (ref "IC27") (pin "7") (pinfunction "7_7") (pintype "passive"))
    )
    (net (code "216") (name "unconnected-(IC27-Pad8)") (class "Default")
      (node (ref "IC27") (pin "8") (pinfunction "8_8") (pintype "passive"))
    )
    (net (code "217") (name "unconnected-(IC27-Pad9)") (class "Default")
      (node (ref "IC27") (pin "9") (pinfunction "9_9") (pintype "passive"))
    )
    (net (code "218") (name "unconnected-(IC27-Pad10)") (class "Default")
      (node (ref "IC27") (pin "10") (pinfunction "10_10") (pintype "passive"))
    )
    (net (code "219") (name "unconnected-(IC27-Pad11)") (class "Default")
      (node (ref "IC27") (pin "11") (pinfunction "11_11") (pintype "passive"))
    )
    (net (code "220") (name "unconnected-(IC27-Pad12)") (class "Default")
      (node (ref "IC27") (pin "12") (pinfunction "12_12") (pintype "passive"))
    )
    (net (code "221") (name "unconnected-(IC27-Pad13)") (class "Default")
      (node (ref "IC27") (pin "13") (pinfunction "13_13") (pintype "passive"))
    )
    (net (code "222") (name "unconnected-(IC27-Pad14)") (class "Default")
      (node (ref "IC27") (pin "14") (pinfunction "14_14") (pintype "passive"))
    )
    (net (code "223") (name "unconnected-(IC27-Pad15)") (class "Default")
      (node (ref "IC27") (pin "15") (pinfunction "15_15") (pintype "passive"))
    )
    (net (code "224") (name "unconnected-(IC27-Pad16)") (class "Default")
      (node (ref "IC27") (pin "16") (pinfunction "16_16") (pintype "passive"))
    )
    (net (code "225") (name "unconnected-(IC27-Pad17)") (class "Default")
      (node (ref "IC27") (pin "17") (pinfunction "17_17") (pintype "passive"))
    )
    (net (code "226") (name "unconnected-(IC27-Pad18)") (class "Default")
      (node (ref "IC27") (pin "18") (pinfunction "18_18") (pintype "passive"))
    )
    (net (code "227") (name "unconnected-(IC27-Pad19)") (class "Default")
      (node (ref "IC27") (pin "19") (pinfunction "19_19") (pintype "passive"))
    )
    (net (code "228") (name "unconnected-(IC27-Pad20)") (class "Default")
      (node (ref "IC27") (pin "20") (pinfunction "20_20") (pintype "passive"))
    )
    (net (code "229") (name "unconnected-(IC29A-Y3-Pad12)") (class "Default")
      (node (ref "IC29") (pin "12") (pinfunction "Y3_12") (pintype "output"))
    )
    (net (code "230") (name "unconnected-(IC29A-Y5-Pad10)") (class "Default")
      (node (ref "IC29") (pin "10") (pinfunction "Y5_10") (pintype "output"))
    )
    (net (code "231") (name "unconnected-(IC29A-Y6-Pad9)") (class "Default")
      (node (ref "IC29") (pin "9") (pinfunction "Y6_9") (pintype "output"))
    )
    (net (code "232") (name "unconnected-(IC29A-Y7-Pad7)") (class "Default")
      (node (ref "IC29") (pin "7") (pinfunction "Y7_7") (pintype "output"))
    )
    (net (code "233") (name "unconnected-(IC32A-Y3-Pad12)") (class "Default")
      (node (ref "IC32") (pin "12") (pinfunction "Y3_12") (pintype "output"))
    )
    (net (code "234") (name "unconnected-(IC32A-Y5-Pad10)") (class "Default")
      (node (ref "IC32") (pin "10") (pinfunction "Y5_10") (pintype "output"))
    )
    (net (code "235") (name "unconnected-(IC32A-Y6-Pad9)") (class "Default")
      (node (ref "IC32") (pin "9") (pinfunction "Y6_9") (pintype "output"))
    )
    (net (code "236") (name "unconnected-(IC32A-Y7-Pad7)") (class "Default")
      (node (ref "IC32") (pin "7") (pinfunction "Y7_7") (pintype "output"))
    )
    (net (code "237") (name "unconnected-(IC35B-Y2-Pad7)") (class "Default")
      (node (ref "IC35") (pin "7") (pinfunction "Y2_7") (pintype "tri_state"))
    )
    (net (code "238") (name "unconnected-(IC35B-Y3-Pad5)") (class "Default")
      (node (ref "IC35") (pin "5") (pinfunction "Y3_5") (pintype "tri_state"))
    )
    (net (code "239") (name "unconnected-(IC35B-Y4-Pad3)") (class "Default")
      (node (ref "IC35") (pin "3") (pinfunction "Y4_3") (pintype "tri_state"))
    )
    (net (code "240") (name "unconnected-(IC41A-Y1-Pad5)") (class "Default")
      (node (ref "IC41") (pin "5") (pinfunction "Y1_5") (pintype "output"))
    )
    (net (code "241") (name "unconnected-(IC41A-Y2-Pad6)") (class "Default")
      (node (ref "IC41") (pin "6") (pinfunction "Y2_6") (pintype "output"))
    )
    (net (code "242") (name "unconnected-(IC41B-Y1-Pad11)") (class "Default")
      (node (ref "IC41") (pin "11") (pinfunction "Y1_11") (pintype "output"))
    )
    (net (code "243") (name "unconnected-(IC41B-Y2-Pad10)") (class "Default")
      (node (ref "IC41") (pin "10") (pinfunction "Y2_10") (pintype "output"))
    )
    (net (code "244") (name "unconnected-(INTENBA-BO-Pad13)") (class "Default")
      (node (ref "INTENB") (pin "13") (pinfunction "BO_13") (pintype "output"))
    )
    (net (code "245") (name "unconnected-(INTENBA-CO-Pad12)") (class "Default")
      (node (ref "INTENB") (pin "12") (pinfunction "CO_12") (pintype "output"))
    )
    (net (code "246") (name "unconnected-(INTENBA-QD-Pad7)") (class "Default")
      (node (ref "INTENB") (pin "7") (pinfunction "QD_7") (pintype "output"))
    )
    (net (code "247") (name "unconnected-(SV1-Pad7)") (class "Default")
      (node (ref "SV1") (pin "7") (pinfunction "7_7") (pintype "passive"))
    )
    (net (code "248") (name "unconnected-(SV1-Pad13)") (class "Default")
      (node (ref "SV1") (pin "13") (pinfunction "13_13") (pintype "passive"))
    )
    (net (code "249") (name "~{3CYC}") (class "Default")
      (node (ref "C35L") (pin "28") (pinfunction "28_28") (pintype "passive"))
      (node (ref "J2") (pin "1") (pinfunction "1_1") (pintype "passive"))
    )
    (net (code "250") (name "~{601}") (class "Default")
      (node (ref "IC11") (pin "13") (pinfunction "CLR_13") (pintype "input"))
      (node (ref "IC18") (pin "4") (pinfunction "I0_4") (pintype "input"))
      (node (ref "IC18") (pin "5") (pinfunction "I1_5") (pintype "input"))
      (node (ref "IC23") (pin "1") (pinfunction "CLR_1") (pintype "input"))
      (node (ref "IC32") (pin "15") (pinfunction "Y0_15") (pintype "output"))
      (node (ref "IC9") (pin "1") (pinfunction "CLR_1") (pintype "input"))
      (node (ref "IC9") (pin "13") (pinfunction "CLR_13") (pintype "input"))
    )
    (net (code "251") (name "~{602}") (class "Default")
      (node (ref "IC10") (pin "1") (pinfunction "CLR_1") (pintype "input"))
      (node (ref "IC18") (pin "1") (pinfunction "I0_1") (pintype "input"))
      (node (ref "IC18") (pin "12") (pinfunction "I0_12") (pintype "input"))
      (node (ref "IC29") (pin "15") (pinfunction "Y0_15") (pintype "output"))
    )
    (net (code "252") (name "~{604}") (class "Default")
      (node (ref "IC10") (pin "4") (pinfunction "PRE_4") (pintype "input"))
      (node (ref "IC18") (pin "13") (pinfunction "I1_13") (pintype "input"))
      (node (ref "IC18") (pin "2") (pinfunction "I1_2") (pintype "input"))
      (node (ref "IC25") (pin "15") (pinfunction "Y0_15") (pintype "output"))
    )
    (net (code "253") (name "~{611}") (class "Default")
      (node (ref "FIELD") (pin "14") (pinfunction "CLR_14") (pintype "input"))
      (node (ref "IC32") (pin "14") (pinfunction "Y1_14") (pintype "output"))
      (node (ref "INTENB") (pin "14") (pinfunction "CLR_14") (pintype "input"))
    )
    (net (code "254") (name "~{612}") (class "Default")
      (node (ref "IC19") (pin "5") (pinfunction "I_5") (pintype "input"))
      (node (ref "IC29") (pin "14") (pinfunction "Y1_14") (pintype "output"))
    )
    (net (code "255") (name "~{614}") (class "Default")
      (node (ref "IC17") (pin "13") (pinfunction "B_13") (pintype "input"))
      (node (ref "IC22") (pin "3") (pinfunction "I_3") (pintype "input"))
      (node (ref "IC25") (pin "14") (pinfunction "Y1_14") (pintype "output"))
    )
    (net (code "256") (name "~{621}") (class "Default")
      (node (ref "IC32") (pin "13") (pinfunction "Y2_13") (pintype "output"))
      (node (ref "IC7") (pin "3") (pinfunction "B_3") (pintype "input"))
    )
    (net (code "257") (name "~{622}") (class "Default")
      (node (ref "IC29") (pin "13") (pinfunction "Y2_13") (pintype "output"))
      (node (ref "IC7") (pin "13") (pinfunction "B_13") (pintype "input"))
    )
    (net (code "258") (name "~{624}") (class "Default")
      (node (ref "IC22") (pin "13") (pinfunction "I_13") (pintype "input"))
      (node (ref "IC24") (pin "1") (pinfunction "G_1") (pintype "input"))
      (node (ref "IC25") (pin "13") (pinfunction "Y2_13") (pintype "output"))
      (node (ref "IC31") (pin "1") (pinfunction "G_1") (pintype "input"))
      (node (ref "IC38") (pin "1") (pinfunction "G_1") (pintype "input"))
    )
    (net (code "259") (name "~{641}") (class "Default")
      (node (ref "IC16") (pin "13") (pinfunction "B_13") (pintype "input"))
      (node (ref "IC32") (pin "11") (pinfunction "Y4_11") (pintype "output"))
    )
    (net (code "260") (name "~{642}") (class "Default")
      (node (ref "DAR4-7") (pin "11") (pinfunction "LD_11") (pintype "input"))
      (node (ref "DAR8-11") (pin "11") (pinfunction "LD_11") (pintype "input"))
      (node (ref "IC29") (pin "11") (pinfunction "Y4_11") (pintype "output"))
    )
    (net (code "261") (name "~{644}") (class "Default")
      (node (ref "IC16") (pin "3") (pinfunction "B_3") (pintype "input"))
      (node (ref "IC25") (pin "11") (pinfunction "Y4_11") (pintype "output"))
    )
    (net (code "262") (name "~{645}") (class "Default")
      (node (ref "IC16") (pin "4") (pinfunction "Y0_4") (pintype "output"))
      (node (ref "IC24") (pin "19") (pinfunction "G_19") (pintype "input"))
      (node (ref "IC31") (pin "19") (pinfunction "G_19") (pintype "input"))
      (node (ref "IC38") (pin "19") (pinfunction "G_19") (pintype "input"))
    )
    (net (code "263") (name "~{ACB00}") (class "Default")
      (node (ref "D34L") (pin "2") (pinfunction "2_2") (pintype "passive"))
      (node (ref "IC37") (pin "12") (pinfunction "Y4_12") (pintype "tri_state"))
      (node (ref "IC38") (pin "12") (pinfunction "Y4_12") (pintype "tri_state"))
      (node (ref "IC38") (pin "3") (pinfunction "Y4_3") (pintype "tri_state"))
    )
    (net (code "264") (name "~{ACB01}") (class "Default")
      (node (ref "D34L") (pin "4") (pinfunction "4_4") (pintype "passive"))
      (node (ref "IC37") (pin "14") (pinfunction "Y3_14") (pintype "tri_state"))
      (node (ref "IC38") (pin "14") (pinfunction "Y3_14") (pintype "tri_state"))
      (node (ref "IC38") (pin "5") (pinfunction "Y3_5") (pintype "tri_state"))
    )
    (net (code "265") (name "~{ACB02}") (class "Default")
      (node (ref "D34L") (pin "6") (pinfunction "6_6") (pintype "passive"))
      (node (ref "IC37") (pin "16") (pinfunction "Y2_16") (pintype "tri_state"))
      (node (ref "IC38") (pin "16") (pinfunction "Y2_16") (pintype "tri_state"))
      (node (ref "IC38") (pin "7") (pinfunction "Y2_7") (pintype "tri_state"))
    )
    (net (code "266") (name "~{ACB03}") (class "Default")
      (node (ref "D34L") (pin "8") (pinfunction "8_8") (pintype "passive"))
      (node (ref "IC37") (pin "18") (pinfunction "Y1_18") (pintype "tri_state"))
      (node (ref "IC38") (pin "18") (pinfunction "Y1_18") (pintype "tri_state"))
      (node (ref "IC38") (pin "9") (pinfunction "Y1_9") (pintype "tri_state"))
    )
    (net (code "267") (name "~{ACB04}") (class "Default")
      (node (ref "D34L") (pin "10") (pinfunction "10_10") (pintype "passive"))
      (node (ref "IC30") (pin "3") (pinfunction "Y4_3") (pintype "tri_state"))
      (node (ref "IC31") (pin "12") (pinfunction "Y4_12") (pintype "tri_state"))
      (node (ref "IC31") (pin "3") (pinfunction "Y4_3") (pintype "tri_state"))
    )
    (net (code "268") (name "~{ACB05}") (class "Default")
      (node (ref "D34L") (pin "12") (pinfunction "12_12") (pintype "passive"))
      (node (ref "IC30") (pin "5") (pinfunction "Y3_5") (pintype "tri_state"))
      (node (ref "IC31") (pin "14") (pinfunction "Y3_14") (pintype "tri_state"))
      (node (ref "IC31") (pin "5") (pinfunction "Y3_5") (pintype "tri_state"))
    )
    (net (code "269") (name "~{ACB06}") (class "Default")
      (node (ref "D34L") (pin "14") (pinfunction "14_14") (pintype "passive"))
      (node (ref "IC30") (pin "7") (pinfunction "Y2_7") (pintype "tri_state"))
      (node (ref "IC31") (pin "16") (pinfunction "Y2_16") (pintype "tri_state"))
      (node (ref "IC31") (pin "7") (pinfunction "Y2_7") (pintype "tri_state"))
    )
    (net (code "270") (name "~{ACB07}") (class "Default")
      (node (ref "D34L") (pin "16") (pinfunction "16_16") (pintype "passive"))
      (node (ref "IC30") (pin "9") (pinfunction "Y1_9") (pintype "tri_state"))
      (node (ref "IC31") (pin "18") (pinfunction "Y1_18") (pintype "tri_state"))
      (node (ref "IC31") (pin "9") (pinfunction "Y1_9") (pintype "tri_state"))
    )
    (net (code "271") (name "~{ACB08}") (class "Default")
      (node (ref "D34L") (pin "18") (pinfunction "18_18") (pintype "passive"))
      (node (ref "IC24") (pin "12") (pinfunction "Y4_12") (pintype "tri_state"))
      (node (ref "IC24") (pin "3") (pinfunction "Y4_3") (pintype "tri_state"))
      (node (ref "IC30") (pin "12") (pinfunction "Y4_12") (pintype "tri_state"))
    )
    (net (code "272") (name "~{ACB09}") (class "Default")
      (node (ref "D34L") (pin "22") (pinfunction "22_22") (pintype "passive"))
      (node (ref "IC24") (pin "14") (pinfunction "Y3_14") (pintype "tri_state"))
      (node (ref "IC24") (pin "5") (pinfunction "Y3_5") (pintype "tri_state"))
      (node (ref "IC30") (pin "14") (pinfunction "Y3_14") (pintype "tri_state"))
    )
    (net (code "273") (name "~{ACB10}") (class "Default")
      (node (ref "D34L") (pin "24") (pinfunction "24_24") (pintype "passive"))
      (node (ref "IC24") (pin "16") (pinfunction "Y2_16") (pintype "tri_state"))
      (node (ref "IC24") (pin "7") (pinfunction "Y2_7") (pintype "tri_state"))
      (node (ref "IC30") (pin "16") (pinfunction "Y2_16") (pintype "tri_state"))
    )
    (net (code "274") (name "~{ACB11}") (class "Default")
      (node (ref "D34L") (pin "26") (pinfunction "26_26") (pintype "passive"))
      (node (ref "IC24") (pin "18") (pinfunction "Y1_18") (pintype "tri_state"))
      (node (ref "IC24") (pin "9") (pinfunction "Y1_9") (pintype "tri_state"))
      (node (ref "IC30") (pin "18") (pinfunction "Y1_18") (pintype "tri_state"))
    )
    (net (code "275") (name "~{ACCLEAR}") (class "Default")
      (node (ref "D34L") (pin "32") (pinfunction "32_32") (pintype "passive"))
      (node (ref "IC22") (pin "12") (pinfunction "O_12") (pintype "open_collector"))
      (node (ref "IC22") (pin "2") (pinfunction "O_2") (pintype "open_collector"))
      (node (ref "IC22") (pin "4") (pinfunction "O_4") (pintype "open_collector"))
    )
    (net (code "276") (name "~{BADDAC}") (class "Default")
      (node (ref "C36L") (pin "34") (pinfunction "34_34") (pintype "passive"))
      (node (ref "IC11") (pin "1") (pinfunction "CLR_1") (pintype "input"))
    )
    (net (code "277") (name "~{BBREAK}") (class "Default")
      (node (ref "C36L") (pin "32") (pinfunction "32_32") (pintype "passive"))
      (node (ref "DMA8-11") (pin "5") (pinfunction "UP_5") (pintype "input"))
      (node (ref "IC20") (pin "19") (pinfunction "G_19") (pintype "input"))
      (node (ref "IC21") (pin "15") (pinfunction "G_15") (pintype "input"))
      (node (ref "IC41") (pin "1") (pinfunction "G_1") (pintype "input"))
      (node (ref "IC41") (pin "15") (pinfunction "G_15") (pintype "input"))
      (node (ref "IC6") (pin "1") (pinfunction "G_1") (pintype "input"))
    )
    (net (code "278") (name "~{BMB03}") (class "Default")
      (node (ref "D35L") (pin "8") (pinfunction "8_8") (pintype "passive"))
    )
    (net (code "279") (name "~{BMB04}") (class "Default")
      (node (ref "D35L") (pin "12") (pinfunction "12_12") (pintype "passive"))
    )
    (net (code "280") (name "~{BMB05}") (class "Default")
      (node (ref "D35L") (pin "16") (pinfunction "16_16") (pintype "passive"))
    )
    (net (code "281") (name "~{BMB06}") (class "Default")
      (node (ref "D35L") (pin "22") (pinfunction "22_22") (pintype "passive"))
    )
    (net (code "282") (name "~{BMB07}") (class "Default")
      (node (ref "D35L") (pin "26") (pinfunction "26_26") (pintype "passive"))
    )
    (net (code "283") (name "~{BMB08}") (class "Default")
      (node (ref "D35L") (pin "30") (pinfunction "30_30") (pintype "passive"))
    )
    (net (code "284") (name "~{BRK_RQ}") (class "Default")
      (node (ref "C36L") (pin "28") (pinfunction "28_28") (pintype "passive"))
      (node (ref "IC11") (pin "6") (pinfunction "~{Q}_6") (pintype "output"))
      (node (ref "SV1") (pin "11") (pinfunction "11_11") (pintype "passive"))
    )
    (net (code "285") (name "~{BRUN}") (class "Default")
      (node (ref "D34L") (pin "34") (pinfunction "34_34") (pintype "passive"))
    )
    (net (code "286") (name "~{BWC0}") (class "Default")
      (node (ref "C35L") (pin "32") (pinfunction "32_32") (pintype "passive"))
      (node (ref "IC10") (pin "13") (pinfunction "CLR_13") (pintype "input"))
      (node (ref "IC11") (pin "12") (pinfunction "D_12") (pintype "input"))
      (node (ref "SV1") (pin "19") (pinfunction "19_19") (pintype "passive"))
    )
    (net (code "287") (name "~{DA00}") (class "Default")
      (node (ref "C36L") (pin "2") (pinfunction "2_2") (pintype "passive"))
      (node (ref "J14") (pin "1") (pinfunction "1_1") (pintype "passive"))
    )
    (net (code "288") (name "~{DA01}") (class "Default")
      (node (ref "C36L") (pin "4") (pinfunction "4_4") (pintype "passive"))
      (node (ref "J13") (pin "1") (pinfunction "1_1") (pintype "passive"))
    )
    (net (code "289") (name "~{DA02}") (class "Default")
      (node (ref "C36L") (pin "6") (pinfunction "6_6") (pintype "passive"))
      (node (ref "J12") (pin "1") (pinfunction "1_1") (pintype "passive"))
    )
    (net (code "290") (name "~{DA03}") (class "Default")
      (node (ref "C36L") (pin "8") (pinfunction "8_8") (pintype "passive"))
      (node (ref "J11") (pin "1") (pinfunction "1_1") (pintype "passive"))
    )
    (net (code "291") (name "~{DA04}") (class "Default")
      (node (ref "C36L") (pin "10") (pinfunction "10_10") (pintype "passive"))
      (node (ref "J10") (pin "1") (pinfunction "1_1") (pintype "passive"))
    )
    (net (code "292") (name "~{DA05}") (class "Default")
      (node (ref "C36L") (pin "12") (pinfunction "12_12") (pintype "passive"))
      (node (ref "J9") (pin "1") (pinfunction "1_1") (pintype "passive"))
    )
    (net (code "293") (name "~{DA06}") (class "Default")
      (node (ref "C36L") (pin "14") (pinfunction "14_14") (pintype "passive"))
      (node (ref "J8") (pin "1") (pinfunction "1_1") (pintype "passive"))
    )
    (net (code "294") (name "~{DA07}") (class "Default")
      (node (ref "C36L") (pin "16") (pinfunction "16_16") (pintype "passive"))
      (node (ref "J7") (pin "1") (pinfunction "1_1") (pintype "passive"))
    )
    (net (code "295") (name "~{DA08}") (class "Default")
      (node (ref "C36L") (pin "18") (pinfunction "18_18") (pintype "passive"))
      (node (ref "J6") (pin "1") (pinfunction "1_1") (pintype "passive"))
    )
    (net (code "296") (name "~{DA09}") (class "Default")
      (node (ref "C36L") (pin "22") (pinfunction "22_22") (pintype "passive"))
      (node (ref "J5") (pin "1") (pinfunction "1_1") (pintype "passive"))
    )
    (net (code "297") (name "~{DA10}") (class "Default")
      (node (ref "C36L") (pin "24") (pinfunction "24_24") (pintype "passive"))
      (node (ref "J4") (pin "1") (pinfunction "1_1") (pintype "passive"))
    )
    (net (code "298") (name "~{DA11}") (class "Default")
      (node (ref "C36L") (pin "26") (pinfunction "26_26") (pintype "passive"))
      (node (ref "J3") (pin "1") (pinfunction "1_1") (pintype "passive"))
    )
    (net (code "299") (name "~{DATA00}") (class "Default")
      (node (ref "C35L") (pin "2") (pinfunction "2_2") (pintype "passive"))
      (node (ref "IC34") (pin "12") (pinfunction "Y4_12") (pintype "tri_state"))
    )
    (net (code "300") (name "~{DATA01}") (class "Default")
      (node (ref "C35L") (pin "4") (pinfunction "4_4") (pintype "passive"))
      (node (ref "IC34") (pin "14") (pinfunction "Y3_14") (pintype "tri_state"))
    )
    (net (code "301") (name "~{DATA02}") (class "Default")
      (node (ref "C35L") (pin "6") (pinfunction "6_6") (pintype "passive"))
      (node (ref "IC34") (pin "16") (pinfunction "Y2_16") (pintype "tri_state"))
    )
    (net (code "302") (name "~{DATA03}") (class "Default")
      (node (ref "C35L") (pin "8") (pinfunction "8_8") (pintype "passive"))
      (node (ref "IC34") (pin "18") (pinfunction "Y1_18") (pintype "tri_state"))
    )
    (net (code "303") (name "~{DATA04}") (class "Default")
      (node (ref "C35L") (pin "10") (pinfunction "10_10") (pintype "passive"))
      (node (ref "IC26") (pin "3") (pinfunction "Y4_3") (pintype "tri_state"))
    )
    (net (code "304") (name "~{DATA05}") (class "Default")
      (node (ref "C35L") (pin "12") (pinfunction "12_12") (pintype "passive"))
      (node (ref "IC26") (pin "5") (pinfunction "Y3_5") (pintype "tri_state"))
    )
    (net (code "305") (name "~{DATA06}") (class "Default")
      (node (ref "C35L") (pin "14") (pinfunction "14_14") (pintype "passive"))
      (node (ref "IC26") (pin "7") (pinfunction "Y2_7") (pintype "tri_state"))
    )
    (net (code "306") (name "~{DATA07}") (class "Default")
      (node (ref "C35L") (pin "16") (pinfunction "16_16") (pintype "passive"))
      (node (ref "IC26") (pin "9") (pinfunction "Y1_9") (pintype "tri_state"))
    )
    (net (code "307") (name "~{DATA08}") (class "Default")
      (node (ref "C35L") (pin "18") (pinfunction "18_18") (pintype "passive"))
      (node (ref "IC26") (pin "12") (pinfunction "Y4_12") (pintype "tri_state"))
    )
    (net (code "308") (name "~{DATA09}") (class "Default")
      (node (ref "C35L") (pin "22") (pinfunction "22_22") (pintype "passive"))
      (node (ref "IC26") (pin "14") (pinfunction "Y3_14") (pintype "tri_state"))
    )
    (net (code "309") (name "~{DATA10}") (class "Default")
      (node (ref "C35L") (pin "24") (pinfunction "24_24") (pintype "passive"))
      (node (ref "IC26") (pin "16") (pinfunction "Y2_16") (pintype "tri_state"))
    )
    (net (code "310") (name "~{DATA11}") (class "Default")
      (node (ref "C35L") (pin "26") (pinfunction "26_26") (pintype "passive"))
      (node (ref "IC26") (pin "18") (pinfunction "Y1_18") (pintype "tri_state"))
    )
    (net (code "311") (name "~{DCXA}") (class "Default")
      (node (ref "IC16") (pin "12") (pinfunction "Y0_12") (pintype "output"))
      (node (ref "IC18") (pin "10") (pinfunction "I1_10") (pintype "input"))
      (node (ref "IC18") (pin "9") (pinfunction "I0_9") (pintype "input"))
    )
    (net (code "312") (name "~{DIMA}") (class "Default")
      (node (ref "IC17") (pin "11") (pinfunction "Y1_11") (pintype "output"))
      (node (ref "IC30") (pin "1") (pinfunction "G_1") (pintype "input"))
      (node (ref "IC30") (pin "19") (pinfunction "G_19") (pintype "input"))
      (node (ref "IC37") (pin "1") (pinfunction "G_1") (pintype "input"))
    )
    (net (code "313") (name "~{DIML}") (class "Default")
      (node (ref "FIELD") (pin "11") (pinfunction "LD_11") (pintype "input"))
      (node (ref "IC17") (pin "12") (pinfunction "Y0_12") (pintype "output"))
      (node (ref "INTENB") (pin "11") (pinfunction "LD_11") (pintype "input"))
    )
    (net (code "314") (name "~{DMA-IN}") (class "Default")
      (node (ref "IC13") (pin "4") (pinfunction "OI_4") (pintype "input"))
      (node (ref "IC26") (pin "1") (pinfunction "G_1") (pintype "input"))
      (node (ref "IC26") (pin "19") (pinfunction "G_19") (pintype "input"))
      (node (ref "IC34") (pin "1") (pinfunction "G_1") (pintype "input"))
      (node (ref "IC41") (pin "12") (pinfunction "Y0_12") (pintype "output"))
    )
    (net (code "315") (name "~{DMA-OUT}") (class "Default")
      (node (ref "IC28") (pin "1") (pinfunction "G_1") (pintype "input"))
      (node (ref "IC28") (pin "19") (pinfunction "G_19") (pintype "input"))
      (node (ref "IC35") (pin "1") (pinfunction "G_1") (pintype "input"))
      (node (ref "IC35") (pin "19") (pinfunction "G_19") (pintype "input"))
      (node (ref "IC41") (pin "9") (pinfunction "Y3_9") (pintype "output"))
    )
    (net (code "316") (name "~{DRV01}") (class "Default")
      (node (ref "IC41") (pin "4") (pinfunction "Y0_4") (pintype "output"))
      (node (ref "RS08") (pin "38") (pinfunction "38_38") (pintype "passive"))
    )
    (net (code "317") (name "~{DRV23}") (class "Default")
      (node (ref "IC41") (pin "7") (pinfunction "Y3_7") (pintype "output"))
      (node (ref "RS08") (pin "22") (pinfunction "22_22") (pintype "passive"))
    )
    (net (code "318") (name "~{DRVOK}") (class "Default")
      (node (ref "IC21") (pin "13") (pinfunction "B_13") (pintype "input"))
      (node (ref "IC21") (pin "14") (pinfunction "A_14") (pintype "input"))
      (node (ref "R2") (pin "1") (pinfunction "1_1") (pintype "passive"))
      (node (ref "RS08") (pin "40") (pinfunction "40_40") (pintype "passive"))
    )
    (net (code "319") (name "~{EXAD0}") (class "Default")
      (node (ref "C35L") (pin "34") (pinfunction "34_34") (pintype "passive"))
      (node (ref "IC20") (pin "9") (pinfunction "Y1_9") (pintype "tri_state"))
    )
    (net (code "320") (name "~{EXAD1}") (class "Default")
      (node (ref "C35L") (pin "36") (pinfunction "36_36") (pintype "passive"))
      (node (ref "IC20") (pin "7") (pinfunction "Y2_7") (pintype "tri_state"))
    )
    (net (code "321") (name "~{EXAD2}") (class "Default")
      (node (ref "C35L") (pin "38") (pinfunction "38_38") (pintype "passive"))
      (node (ref "IC20") (pin "5") (pinfunction "Y3_5") (pintype "tri_state"))
    )
    (net (code "322") (name "~{INT_RQ}") (class "Default")
      (node (ref "D34L") (pin "30") (pinfunction "30_30") (pintype "passive"))
      (node (ref "IC55") (pin "3") (pinfunction "O_3") (pintype "open_collector"))
      (node (ref "IC55") (pin "6") (pinfunction "O_6") (pintype "open_collector"))
      (node (ref "IC55") (pin "8") (pinfunction "O_8") (pintype "open_collector"))
    )
    (net (code "323") (name "~{IOS}") (class "Default")
      (node (ref "D34L") (pin "28") (pinfunction "28_28") (pintype "passive"))
      (node (ref "IC22") (pin "10") (pinfunction "O_10") (pintype "open_collector"))
    )
    (net (code "324") (name "~{MEM_INC}") (class "Default")
      (node (ref "C36L") (pin "36") (pinfunction "36_36") (pintype "passive"))
    )
    (net (code "325") (name "~{MYDEV}") (class "Default")
      (node (ref "IC25") (pin "4") (pinfunction "G2A_4") (pintype "input"))
      (node (ref "IC29") (pin "4") (pinfunction "G2A_4") (pintype "input"))
      (node (ref "IC32") (pin "4") (pinfunction "G2A_4") (pintype "input"))
      (node (ref "PAD1") (pin "1") (pinfunction "P_1") (pintype "passive"))
    )
    (net (code "326") (name "~{NXD}") (class "Default")
      (node (ref "IC12") (pin "12") (pinfunction "I0_12") (pintype "input"))
      (node (ref "IC23") (pin "6") (pinfunction "~{Q}_6") (pintype "output"))
    )
    (net (code "327") (name "~{PER}") (class "Default")
      (node (ref "IC12") (pin "4") (pinfunction "I0_4") (pintype "input"))
      (node (ref "IC9") (pin "8") (pinfunction "~{Q}_8") (pintype "output"))
    )
    (net (code "328") (name "~{SETNXD}") (class "Default")
      (node (ref "IC21") (pin "9") (pinfunction "Y3_9") (pintype "output"))
      (node (ref "IC23") (pin "4") (pinfunction "PRE_4") (pintype "input"))
    )
    (net (code "329") (name "~{SETPER}") (class "Default")
      (node (ref "IC13") (pin "5") (pinfunction "EVN_5") (pintype "output"))
      (node (ref "IC9") (pin "10") (pinfunction "PRE_10") (pintype "input"))
    )
    (net (code "330") (name "~{SETWLS}") (class "Default")
      (node (ref "IC6") (pin "7") (pinfunction "Y3_7") (pintype "output"))
      (node (ref "IC9") (pin "4") (pinfunction "PRE_4") (pintype "input"))
    )
    (net (code "331") (name "~{SKIP}") (class "Default")
      (node (ref "IC17") (pin "2") (pinfunction "A_2") (pintype "input"))
      (node (ref "IC19") (pin "10") (pinfunction "O_10") (pintype "open_collector"))
      (node (ref "IC19") (pin "2") (pinfunction "O_2") (pintype "open_collector"))
      (node (ref "IC19") (pin "6") (pinfunction "O_6") (pintype "open_collector"))
      (node (ref "R1") (pin "1") (pinfunction "1_1") (pintype "passive"))
    )
    (net (code "332") (name "~{START}") (class "Default")
      (node (ref "DMA0-3") (pin "11") (pinfunction "LD_11") (pintype "input"))
      (node (ref "DMA4-7") (pin "11") (pinfunction "LD_11") (pintype "input"))
      (node (ref "DMA8-11") (pin "11") (pinfunction "LD_11") (pintype "input"))
      (node (ref "IC18") (pin "3") (pinfunction "O_3") (pintype "output"))
    )
    (net (code "333") (name "~{WE}") (class "Default")
      (node (ref "IC22") (pin "5") (pinfunction "I_5") (pintype "input"))
      (node (ref "IC6") (pin "5") (pinfunction "Y1_5") (pintype "output"))
      (node (ref "RS08") (pin "8") (pinfunction "8_8") (pintype "passive"))
    )
    (net (code "334") (name "~{WLS}") (class "Default")
      (node (ref "IC12") (pin "13") (pinfunction "I1_13") (pintype "input"))
      (node (ref "IC9") (pin "6") (pinfunction "~{Q}_6") (pintype "output"))
    )
  )
)
